# module.net
KiCad netlist of a schematic drawn in EAGLE
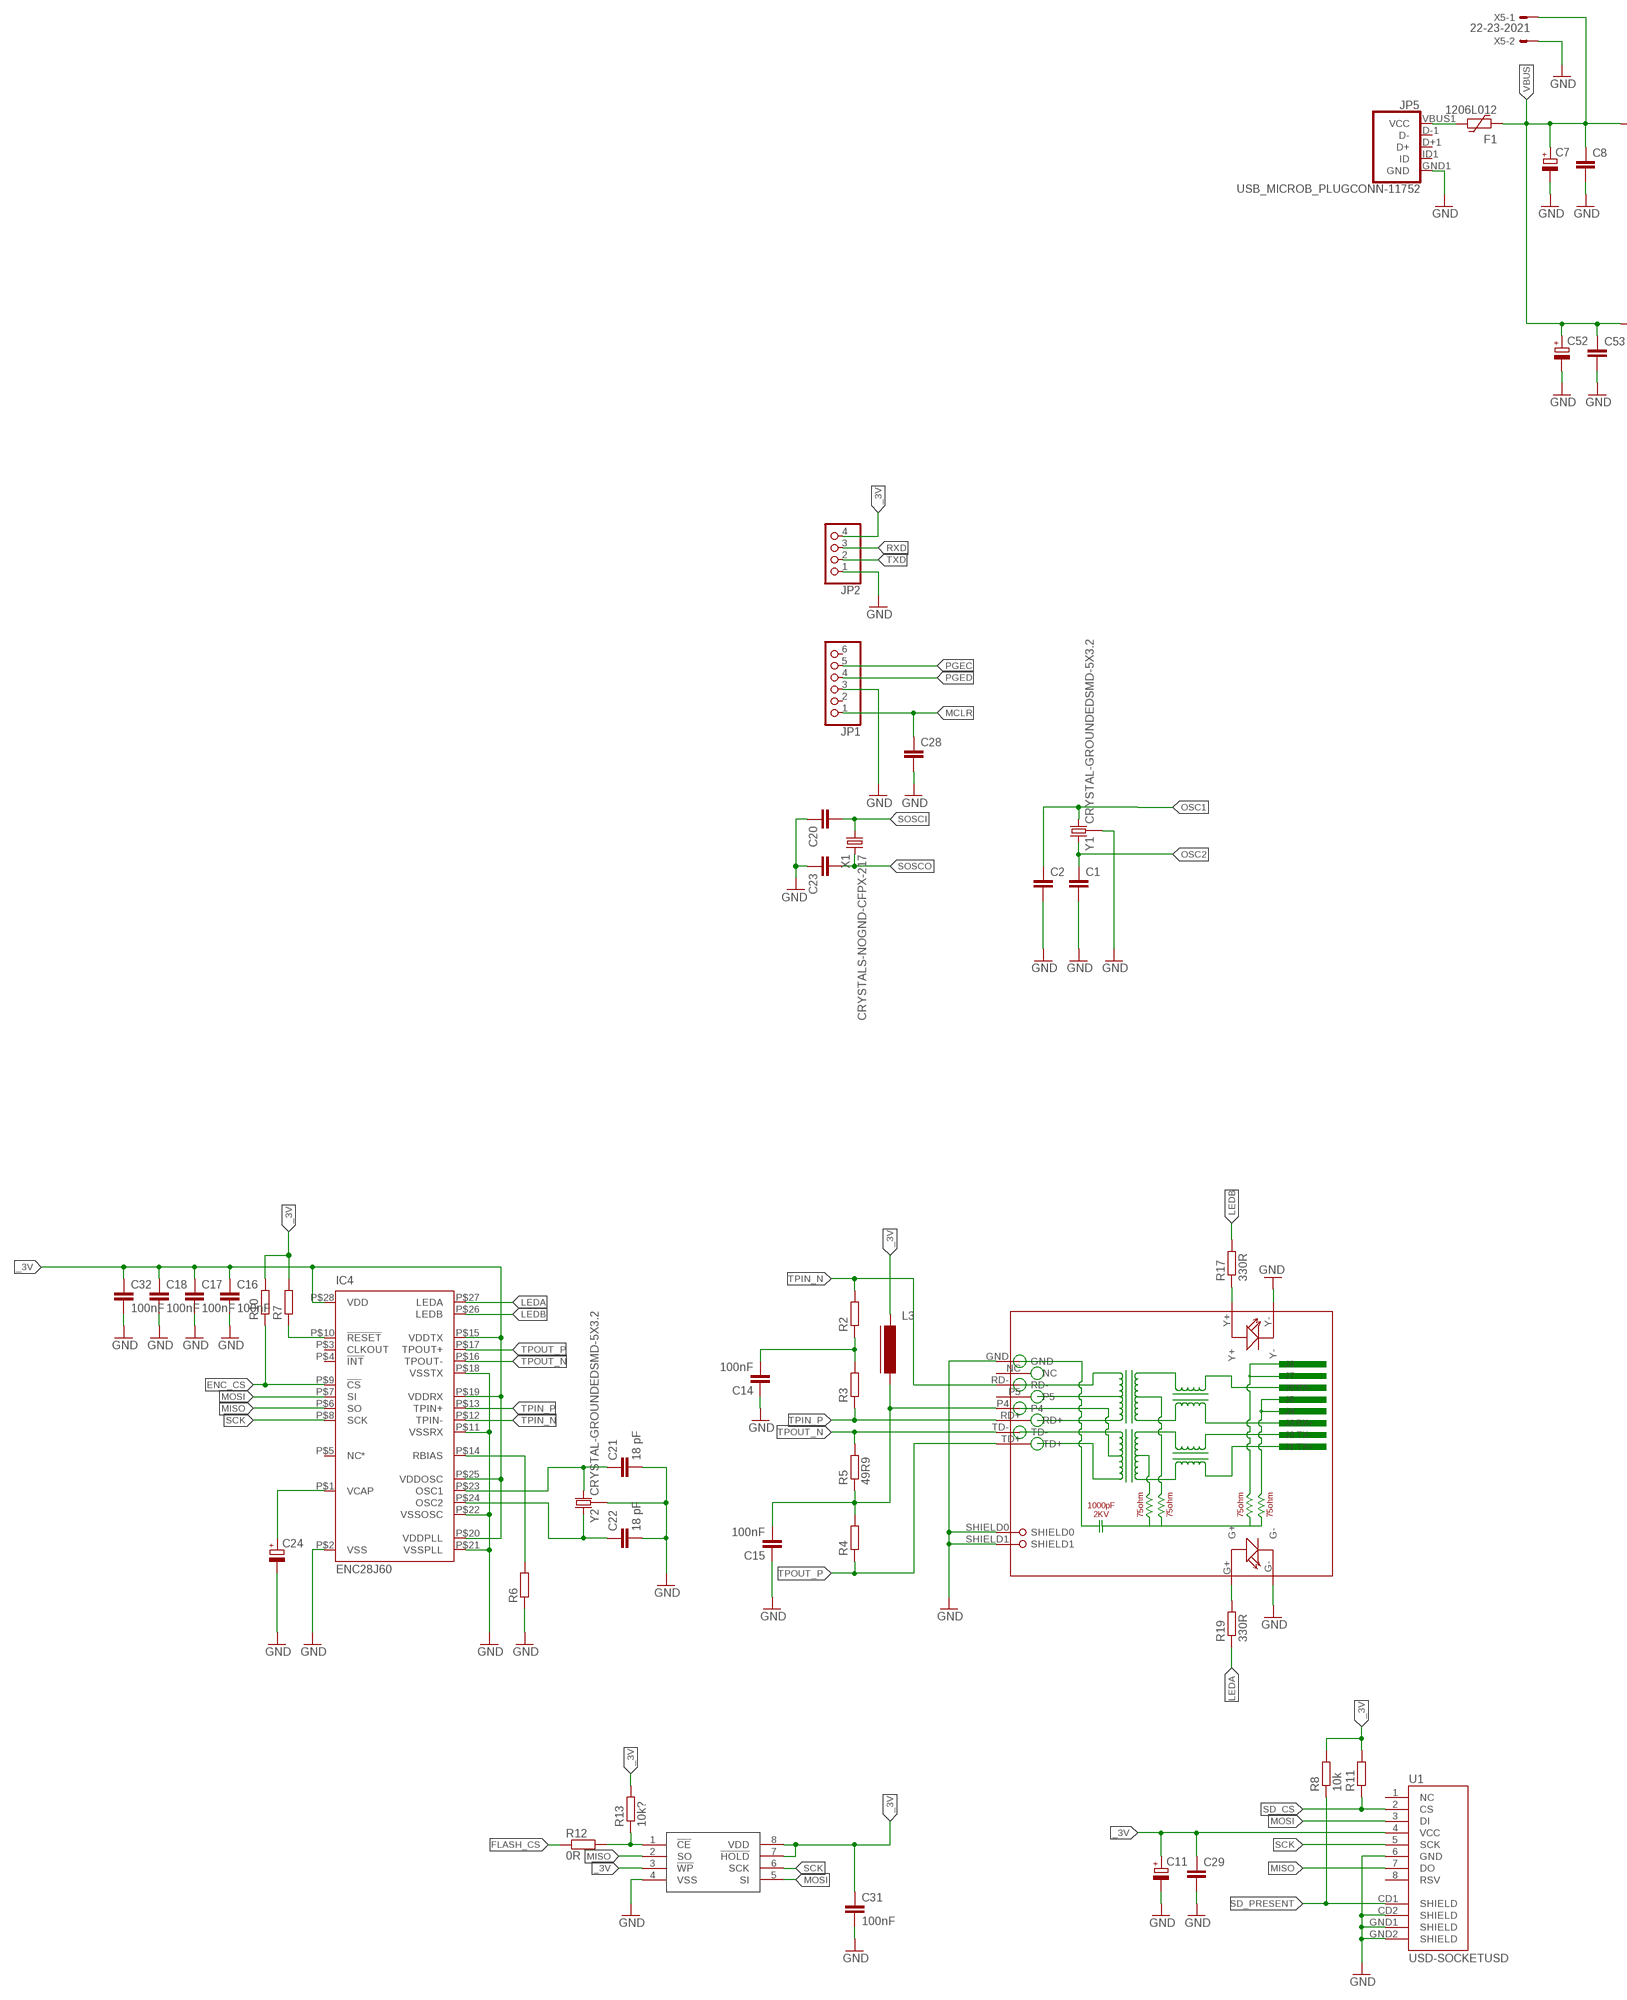
[diagram p0: schematic, sheet 1, part 1 of 3]
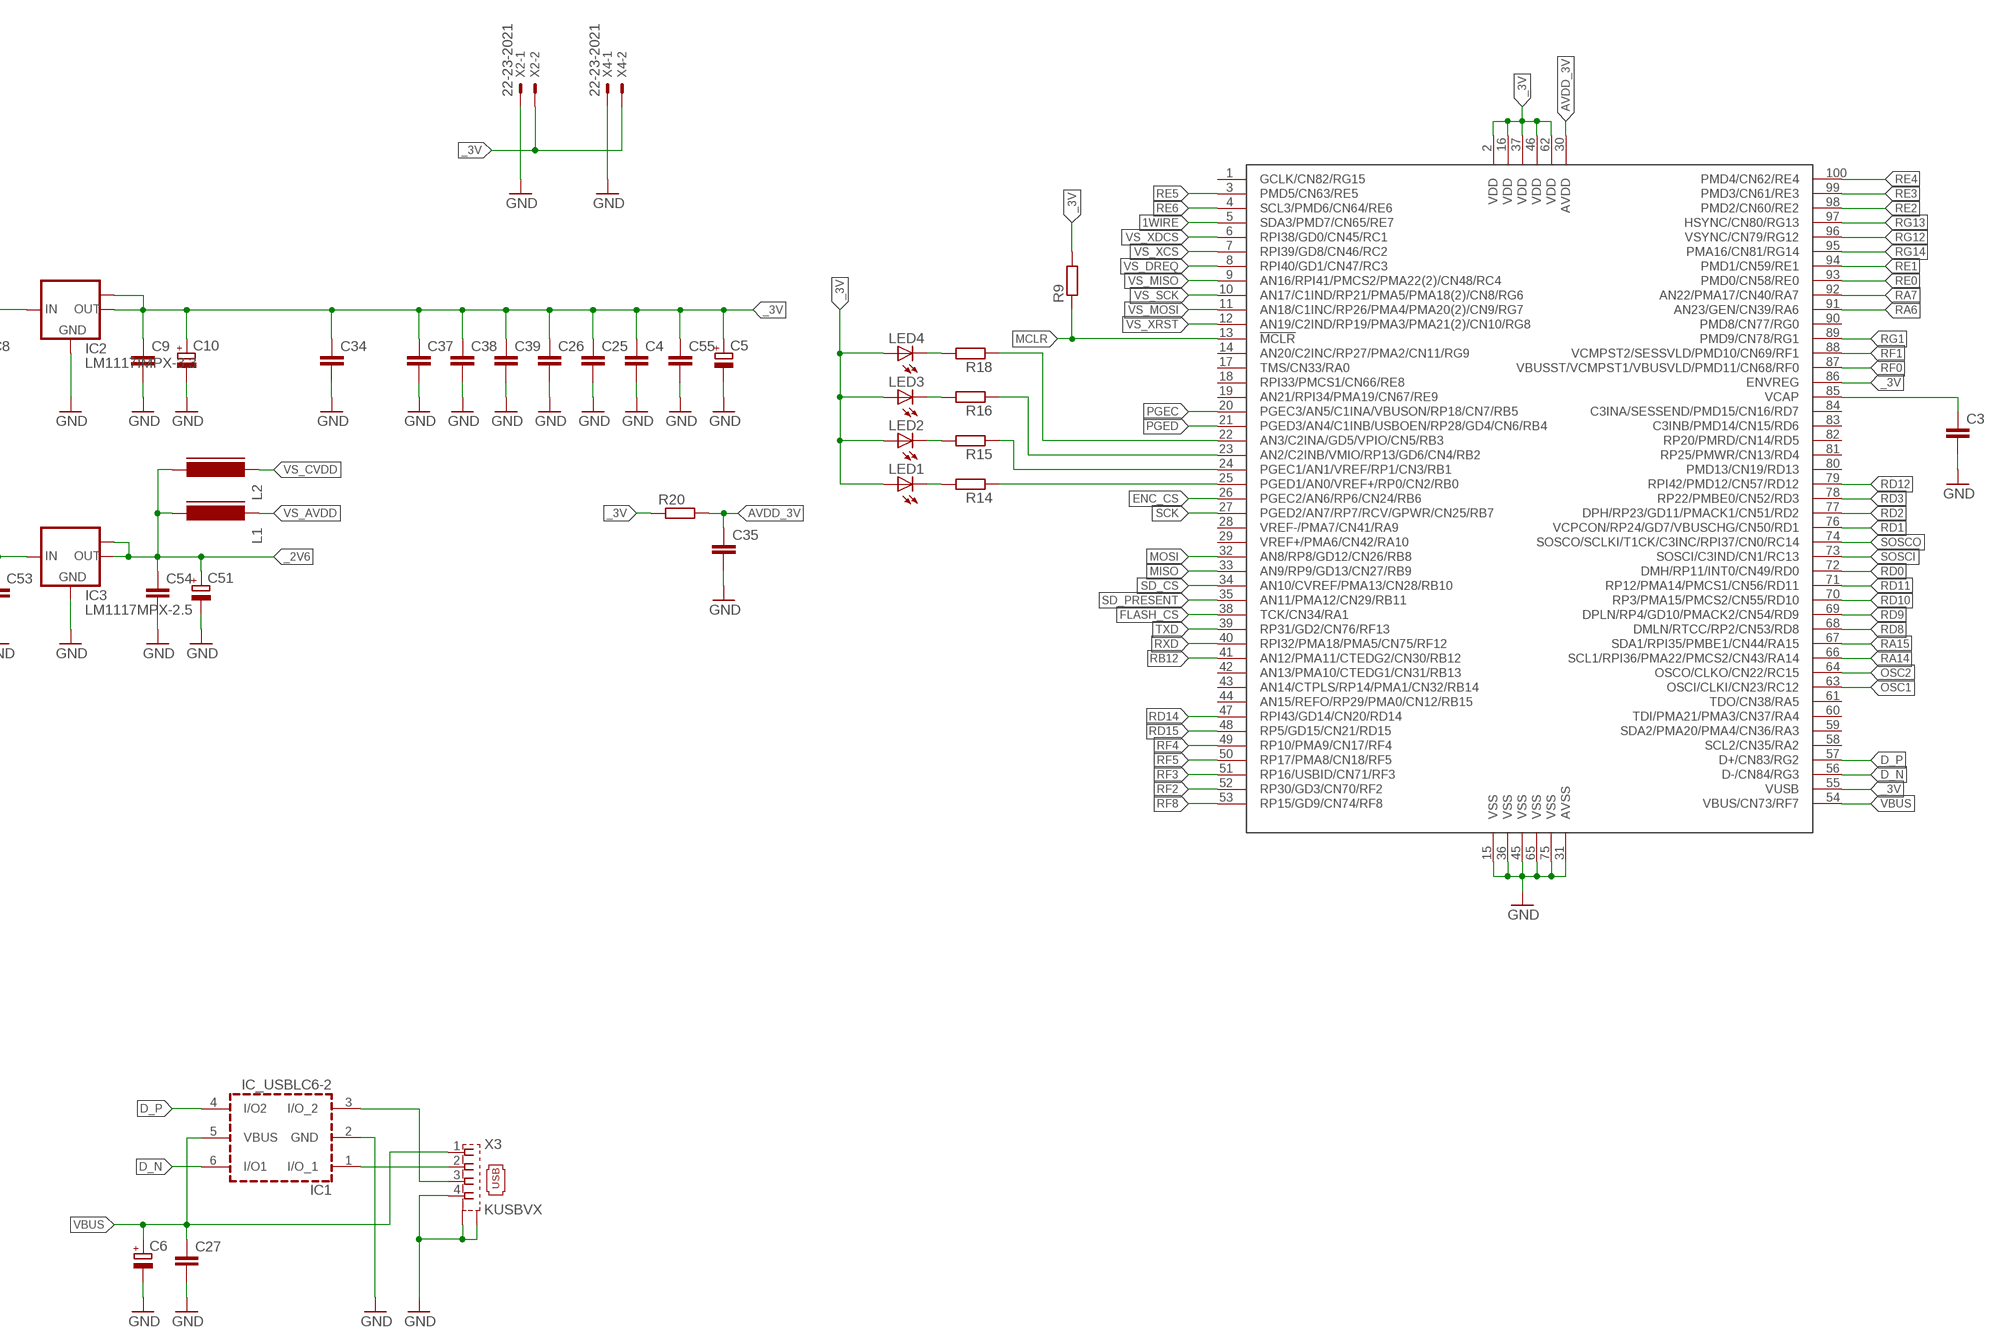
[diagram p1: schematic, sheet 1, part 2 of 3]
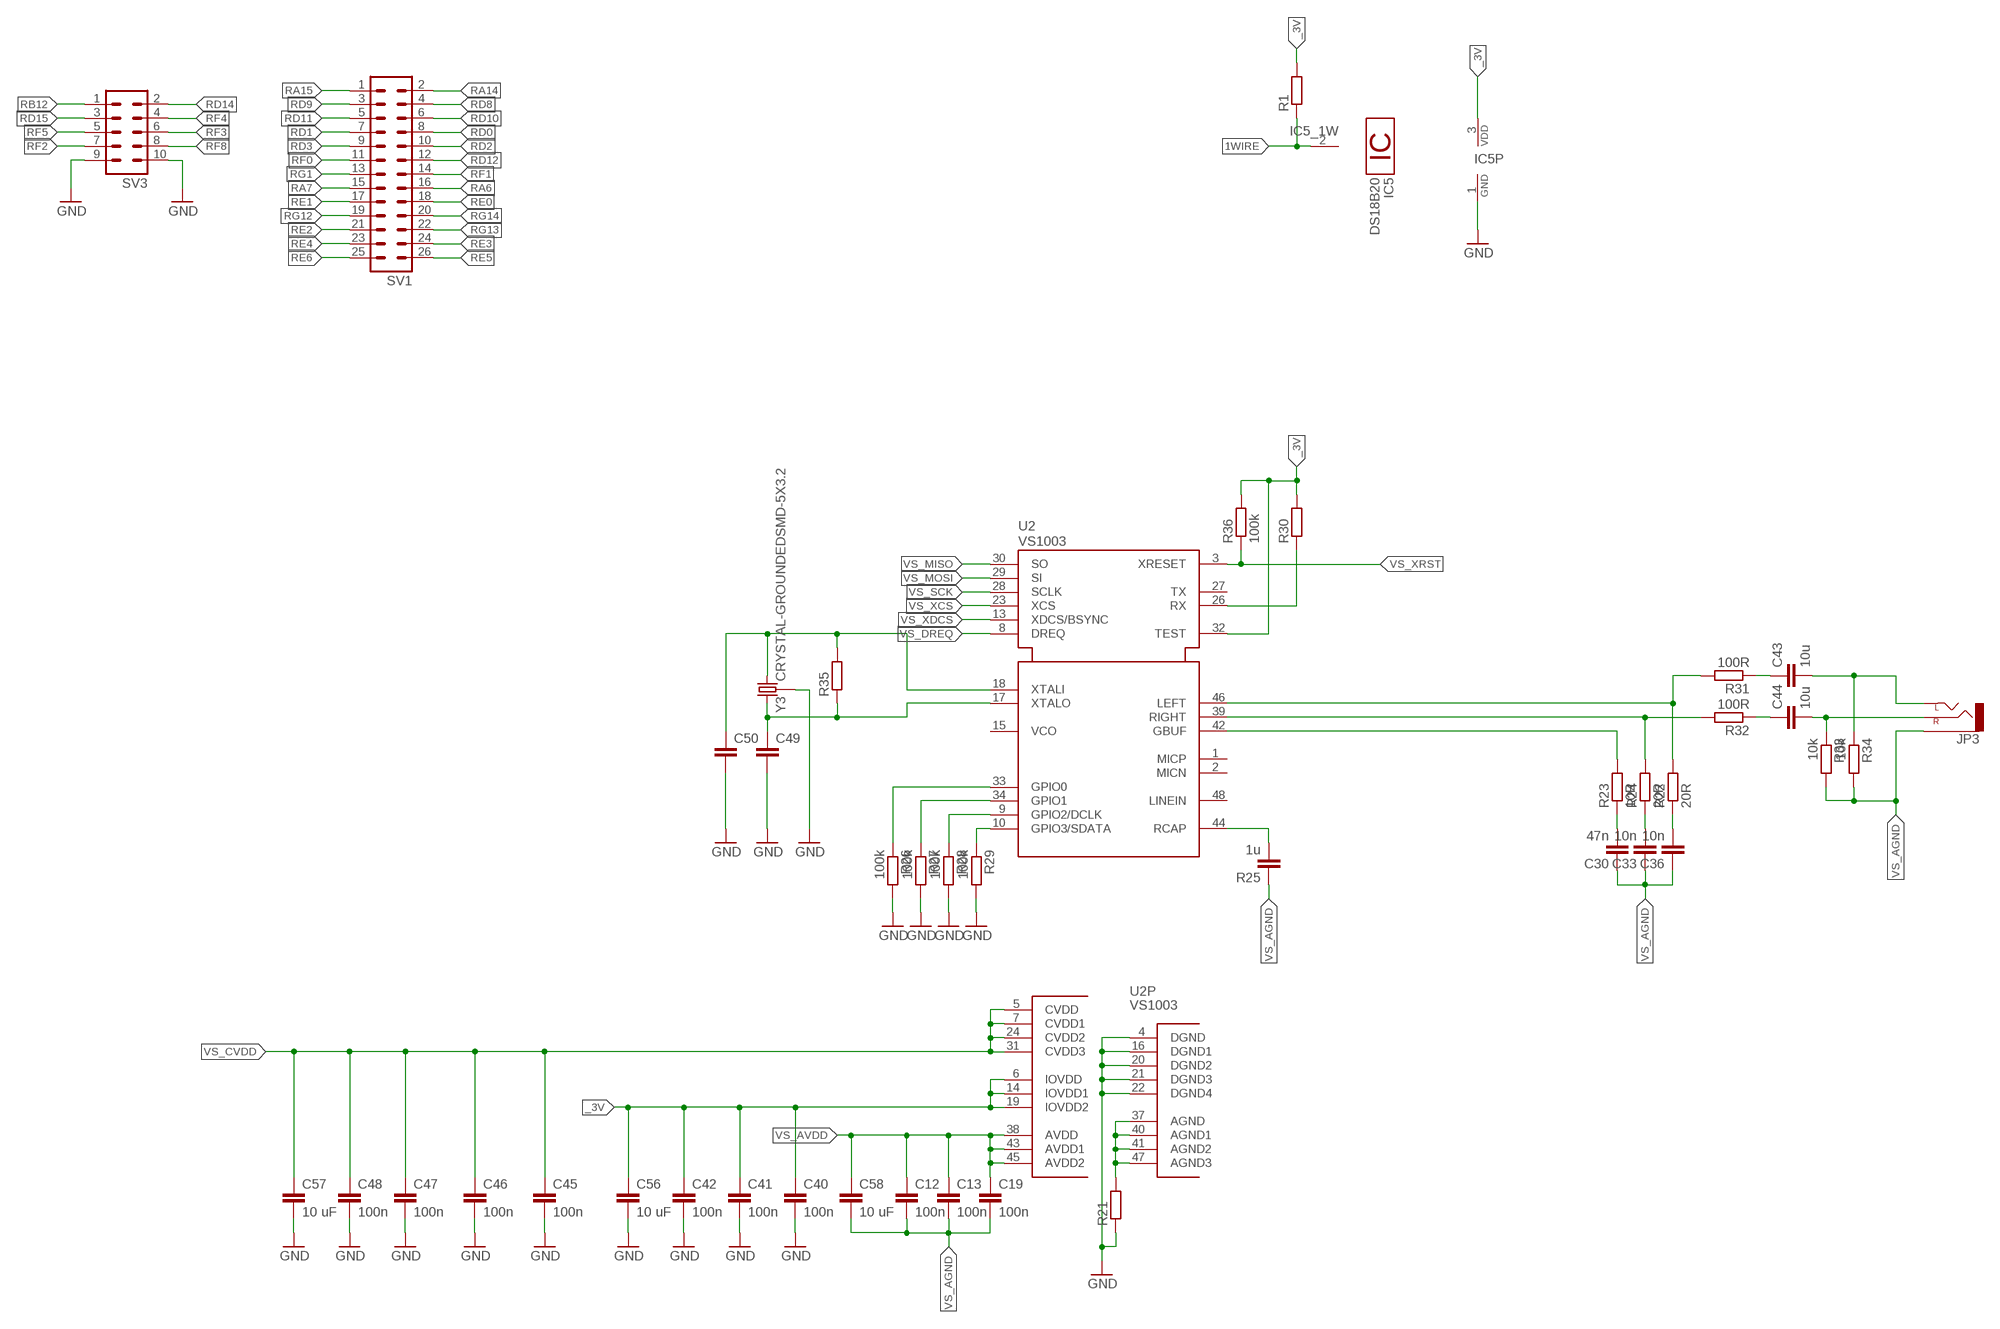
[diagram p2: schematic, sheet 1, part 3 of 3]

(export (version "E")
  (design (tool "Eeschema 10.0.6"))
  (components
    (comp (ref "C1")
      (value "C-EUC0603")
      (footprint "eagle-import:C0603")
      (libsource (lib "eagle-import") (part "C-EUC0603"))
    )
    (comp (ref "C2")
      (value "C-EUC0603")
      (footprint "eagle-import:C0603")
      (libsource (lib "eagle-import") (part "C-EUC0603"))
    )
    (comp (ref "C3")
      (value "C-EUC0603")
      (footprint "eagle-import:C0603")
      (libsource (lib "eagle-import") (part "C-EUC0603"))
    )
    (comp (ref "C4")
      (value "C-EUC0402")
      (footprint "eagle-import:C0402")
      (libsource (lib "eagle-import") (part "C-EUC0402"))
    )
    (comp (ref "C5")
      (value "CPOL-EUSMCA")
      (footprint "eagle-import:SMC_A")
      (libsource (lib "eagle-import") (part "CPOL-EUSMCA"))
    )
    (comp (ref "C6")
      (value "CPOL-EUSMCB")
      (footprint "eagle-import:SMC_B")
      (libsource (lib "eagle-import") (part "CPOL-EUSMCB"))
    )
    (comp (ref "C7")
      (value "CPOL-EUSMCB")
      (footprint "eagle-import:SMC_B")
      (libsource (lib "eagle-import") (part "CPOL-EUSMCB"))
    )
    (comp (ref "C8")
      (value "C-EUC0603")
      (footprint "eagle-import:C0603")
      (libsource (lib "eagle-import") (part "C-EUC0603"))
    )
    (comp (ref "C9")
      (value "C-EUC0603")
      (footprint "eagle-import:C0603")
      (libsource (lib "eagle-import") (part "C-EUC0603"))
    )
    (comp (ref "C10")
      (value "CPOL-EUSMCB")
      (footprint "eagle-import:SMC_B")
      (libsource (lib "eagle-import") (part "CPOL-EUSMCB"))
    )
    (comp (ref "C11")
      (value "CPOL-EUSMCA")
      (footprint "eagle-import:SMC_A")
      (libsource (lib "eagle-import") (part "CPOL-EUSMCA"))
    )
    (comp (ref "C12")
      (value "100n")
      (footprint "eagle-import:C0603")
      (libsource (lib "eagle-import") (part "C-EUC0603"))
    )
    (comp (ref "C13")
      (value "100n")
      (footprint "eagle-import:C0603")
      (libsource (lib "eagle-import") (part "C-EUC0603"))
    )
    (comp (ref "C14")
      (value "100nF")
      (footprint "eagle-import:C0603")
      (libsource (lib "eagle-import") (part "C-EUC0603"))
    )
    (comp (ref "C15")
      (value "100nF")
      (footprint "eagle-import:C0603")
      (libsource (lib "eagle-import") (part "C-EUC0603"))
    )
    (comp (ref "C16")
      (value "100nF")
      (footprint "eagle-import:C0402")
      (libsource (lib "eagle-import") (part "C-EUC0402"))
    )
    (comp (ref "C17")
      (value "100nF")
      (footprint "eagle-import:C0603")
      (libsource (lib "eagle-import") (part "C-EUC0603"))
    )
    (comp (ref "C18")
      (value "100nF")
      (footprint "eagle-import:C0603")
      (libsource (lib "eagle-import") (part "C-EUC0603"))
    )
    (comp (ref "C19")
      (value "100n")
      (footprint "eagle-import:C0603")
      (libsource (lib "eagle-import") (part "C-EUC0603"))
    )
    (comp (ref "C20")
      (value "C-EUC0603")
      (footprint "eagle-import:C0603")
      (libsource (lib "eagle-import") (part "C-EUC0603"))
    )
    (comp (ref "C21")
      (value "18 pF")
      (footprint "eagle-import:C0603")
      (libsource (lib "eagle-import") (part "C-EUC0603"))
    )
    (comp (ref "C22")
      (value "18 pF")
      (footprint "eagle-import:C0603")
      (libsource (lib "eagle-import") (part "C-EUC0603"))
    )
    (comp (ref "C23")
      (value "C-EUC0603")
      (footprint "eagle-import:C0603")
      (libsource (lib "eagle-import") (part "C-EUC0603"))
    )
    (comp (ref "C24")
      (value "CPOL-EUSMCA")
      (footprint "eagle-import:SMC_A")
      (libsource (lib "eagle-import") (part "CPOL-EUSMCA"))
    )
    (comp (ref "C25")
      (value "C-EUC0402")
      (footprint "eagle-import:C0402")
      (libsource (lib "eagle-import") (part "C-EUC0402"))
    )
    (comp (ref "C26")
      (value "C-EUC0402")
      (footprint "eagle-import:C0402")
      (libsource (lib "eagle-import") (part "C-EUC0402"))
    )
    (comp (ref "C27")
      (value "C-EUC0805")
      (footprint "eagle-import:C0805")
      (libsource (lib "eagle-import") (part "C-EUC0805"))
    )
    (comp (ref "C28")
      (value "C-EUC0603")
      (footprint "eagle-import:C0603")
      (libsource (lib "eagle-import") (part "C-EUC0603"))
    )
    (comp (ref "C29")
      (value "C-EUC0603")
      (footprint "eagle-import:C0603")
      (libsource (lib "eagle-import") (part "C-EUC0603"))
    )
    (comp (ref "C30")
      (value "47n")
      (footprint "eagle-import:C0603")
      (libsource (lib "eagle-import") (part "C-EUC0603"))
    )
    (comp (ref "C31")
      (value "100nF")
      (footprint "eagle-import:C0603")
      (libsource (lib "eagle-import") (part "C-EUC0603"))
    )
    (comp (ref "C32")
      (value "100nF")
      (footprint "eagle-import:C0402")
      (libsource (lib "eagle-import") (part "C-EUC0402"))
    )
    (comp (ref "C33")
      (value "10n")
      (footprint "eagle-import:C0603")
      (libsource (lib "eagle-import") (part "C-EUC0603"))
    )
    (comp (ref "C34")
      (value "C-EUC0402")
      (footprint "eagle-import:C0402")
      (libsource (lib "eagle-import") (part "C-EUC0402"))
    )
    (comp (ref "C35")
      (value "C-EUC0402")
      (footprint "eagle-import:C0402")
      (libsource (lib "eagle-import") (part "C-EUC0402"))
    )
    (comp (ref "C36")
      (value "10n")
      (footprint "eagle-import:C0603")
      (libsource (lib "eagle-import") (part "C-EUC0603"))
    )
    (comp (ref "C37")
      (value "C-EUC0402")
      (footprint "eagle-import:C0402")
      (libsource (lib "eagle-import") (part "C-EUC0402"))
    )
    (comp (ref "C38")
      (value "C-EUC0603")
      (footprint "eagle-import:C0603")
      (libsource (lib "eagle-import") (part "C-EUC0603"))
    )
    (comp (ref "C39")
      (value "C-EUC0402")
      (footprint "eagle-import:C0402")
      (libsource (lib "eagle-import") (part "C-EUC0402"))
    )
    (comp (ref "C40")
      (value "100n")
      (footprint "eagle-import:C0402")
      (libsource (lib "eagle-import") (part "C-EUC0402"))
    )
    (comp (ref "C41")
      (value "100n")
      (footprint "eagle-import:C0402")
      (libsource (lib "eagle-import") (part "C-EUC0402"))
    )
    (comp (ref "C42")
      (value "100n")
      (footprint "eagle-import:C0402")
      (libsource (lib "eagle-import") (part "C-EUC0402"))
    )
    (comp (ref "C43")
      (value "10u")
      (footprint "eagle-import:C0603")
      (libsource (lib "eagle-import") (part "C-EUC0603"))
    )
    (comp (ref "C44")
      (value "10u")
      (footprint "eagle-import:C0603")
      (libsource (lib "eagle-import") (part "C-EUC0603"))
    )
    (comp (ref "C45")
      (value "100n")
      (footprint "eagle-import:C0402")
      (libsource (lib "eagle-import") (part "C-EUC0402"))
    )
    (comp (ref "C46")
      (value "100n")
      (footprint "eagle-import:C0603")
      (libsource (lib "eagle-import") (part "C-EUC0603"))
    )
    (comp (ref "C47")
      (value "100n")
      (footprint "eagle-import:C0603")
      (libsource (lib "eagle-import") (part "C-EUC0603"))
    )
    (comp (ref "C48")
      (value "100n")
      (footprint "eagle-import:C0603")
      (libsource (lib "eagle-import") (part "C-EUC0603"))
    )
    (comp (ref "C49")
      (value "C-EUC0603")
      (footprint "eagle-import:C0603")
      (libsource (lib "eagle-import") (part "C-EUC0603"))
    )
    (comp (ref "C50")
      (value "C-EUC0603")
      (footprint "eagle-import:C0603")
      (libsource (lib "eagle-import") (part "C-EUC0603"))
    )
    (comp (ref "C51")
      (value "CPOL-EUSMCC")
      (footprint "eagle-import:SMC_C")
      (libsource (lib "eagle-import") (part "CPOL-EUSMCC"))
    )
    (comp (ref "C52")
      (value "CPOL-EUSMCC")
      (footprint "eagle-import:SMC_C")
      (libsource (lib "eagle-import") (part "CPOL-EUSMCC"))
    )
    (comp (ref "C53")
      (value "C-EUC1206")
      (footprint "eagle-import:C1206")
      (libsource (lib "eagle-import") (part "C-EUC1206"))
    )
    (comp (ref "C54")
      (value "C-EUC1206")
      (footprint "eagle-import:C1206")
      (libsource (lib "eagle-import") (part "C-EUC1206"))
    )
    (comp (ref "C55")
      (value "C-EUC0603")
      (footprint "eagle-import:C0603")
      (libsource (lib "eagle-import") (part "C-EUC0603"))
    )
    (comp (ref "C56")
      (value "10 uF")
      (footprint "eagle-import:C0603")
      (libsource (lib "eagle-import") (part "C-EUC0603"))
    )
    (comp (ref "C57")
      (value "10 uF")
      (footprint "eagle-import:C0603")
      (libsource (lib "eagle-import") (part "C-EUC0603"))
    )
    (comp (ref "C58")
      (value "10 uF")
      (footprint "eagle-import:C0603")
      (libsource (lib "eagle-import") (part "C-EUC0603"))
    )
    (comp (ref "F1")
      (value "1206L012")
      (footprint "eagle-import:1206L")
      (fields (field (name "MF") "Littelfuse"))
      (libsource (lib "eagle-import") (part "?1206L012"))
    )
    (comp (ref "IC1")
      (value "IC_USBLC6-2")
      (footprint "eagle-import:SOT-23-6L")
      (libsource (lib "eagle-import") (part "IC_USBLC6-2"))
    )
    (comp (ref "IC2")
      (value "LM1117IMPX-3.3")
      (footprint "eagle-import:SOT223")
      (libsource (lib "eagle-import") (part "LM1117IMPX-3.3"))
    )
    (comp (ref "IC3")
      (value "LM1117MPX-2.5")
      (footprint "eagle-import:SOT223")
      (libsource (lib "eagle-import") (part "LM1117MPX-2.5"))
    )
    (comp (ref "IC4")
      (value "ENC28J60")
      (footprint "eagle-import:TSSOP28W")
      (libsource (lib "eagle-import") (part "ENC28J60"))
    )
    (comp (ref "IC5")
      (value "DS18B20")
      (footprint "eagle-import:TO92-")
      (libsource (lib "eagle-import") (part "DS18B20"))
    )
    (comp (ref "JP1")
      (value "PINHD-1X6")
      (footprint "eagle-import:1X06")
      (libsource (lib "eagle-import") (part "PINHD-1X6"))
    )
    (comp (ref "JP2")
      (value "PINHD-1X4")
      (footprint "eagle-import:1X04")
      (libsource (lib "eagle-import") (part "PINHD-1X4"))
    )
    (comp (ref "JP3")
      (value "AUDIO-JACKAUDIO_JACK2")
      (footprint "eagle-import:AUDIO-JACK2")
      (libsource (lib "eagle-import") (part "AUDIO-JACKAUDIO_JACK2"))
    )
    (comp (ref "JP5")
      (value "USB_MICROB_PLUGCONN-11752")
      (footprint "eagle-import:USB-B-MICRO-SMD_V03")
      (libsource (lib "eagle-import") (part "USB_MICROB_PLUGCONN-11752"))
    )
    (comp (ref "L1")
      (value "FERRITE-0805")
      (footprint "eagle-import:FB805")
      (libsource (lib "eagle-import") (part "FERRITE-0805"))
    )
    (comp (ref "L2")
      (value "FERRITE-0805")
      (footprint "eagle-import:FB805")
      (libsource (lib "eagle-import") (part "FERRITE-0805"))
    )
    (comp (ref "L3")
      (value "FERRITE-0805")
      (footprint "eagle-import:FB805")
      (libsource (lib "eagle-import") (part "FERRITE-0805"))
    )
    (comp (ref "LED1")
      (value "LEDCHIP-LED0603")
      (footprint "eagle-import:CHIP-LED0603")
      (libsource (lib "eagle-import") (part "LEDCHIP-LED0603"))
    )
    (comp (ref "LED2")
      (value "LEDCHIP-LED0603")
      (footprint "eagle-import:CHIP-LED0603")
      (libsource (lib "eagle-import") (part "LEDCHIP-LED0603"))
    )
    (comp (ref "LED3")
      (value "LEDCHIP-LED0603")
      (footprint "eagle-import:CHIP-LED0603")
      (libsource (lib "eagle-import") (part "LEDCHIP-LED0603"))
    )
    (comp (ref "LED4")
      (value "LEDCHIP-LED0603")
      (footprint "eagle-import:CHIP-LED0603")
      (libsource (lib "eagle-import") (part "LEDCHIP-LED0603"))
    )
    (comp (ref "R1")
      (value "R-EU_R0603")
      (footprint "eagle-import:R0603")
      (libsource (lib "eagle-import") (part "R-EU_R0603"))
    )
    (comp (ref "R2")
      (value "R-EU_R0603")
      (footprint "eagle-import:R0603")
      (libsource (lib "eagle-import") (part "R-EU_R0603"))
    )
    (comp (ref "R3")
      (value "R-EU_R0603")
      (footprint "eagle-import:R0603")
      (libsource (lib "eagle-import") (part "R-EU_R0603"))
    )
    (comp (ref "R4")
      (value "R-EU_R0603")
      (footprint "eagle-import:R0603")
      (libsource (lib "eagle-import") (part "R-EU_R0603"))
    )
    (comp (ref "R5")
      (value "49R9")
      (footprint "eagle-import:R0603")
      (libsource (lib "eagle-import") (part "R-EU_R0603"))
    )
    (comp (ref "R6")
      (value "R-EU_R0805")
      (footprint "eagle-import:R0805")
      (libsource (lib "eagle-import") (part "R-EU_R0805"))
    )
    (comp (ref "R7")
      (value "R-EU_R0603")
      (footprint "eagle-import:R0603")
      (libsource (lib "eagle-import") (part "R-EU_R0603"))
    )
    (comp (ref "R8")
      (value "10k")
      (footprint "eagle-import:R0603")
      (libsource (lib "eagle-import") (part "R-EU_R0603"))
    )
    (comp (ref "R9")
      (value "R-EU_R0603")
      (footprint "eagle-import:R0603")
      (libsource (lib "eagle-import") (part "R-EU_R0603"))
    )
    (comp (ref "R10")
      (value "R-EU_R0603")
      (footprint "eagle-import:R0603")
      (libsource (lib "eagle-import") (part "R-EU_R0603"))
    )
    (comp (ref "R11")
      (value "R-EU_R0603")
      (footprint "eagle-import:R0603")
      (libsource (lib "eagle-import") (part "R-EU_R0603"))
    )
    (comp (ref "R12")
      (value "0R")
      (footprint "eagle-import:R0603")
      (libsource (lib "eagle-import") (part "R-EU_R0603"))
    )
    (comp (ref "R13")
      (value "10k?")
      (footprint "eagle-import:R0603")
      (libsource (lib "eagle-import") (part "R-EU_R0603"))
    )
    (comp (ref "R14")
      (value "R-EU_R0603")
      (footprint "eagle-import:R0603")
      (libsource (lib "eagle-import") (part "R-EU_R0603"))
    )
    (comp (ref "R15")
      (value "R-EU_R0603")
      (footprint "eagle-import:R0603")
      (libsource (lib "eagle-import") (part "R-EU_R0603"))
    )
    (comp (ref "R16")
      (value "R-EU_R0603")
      (footprint "eagle-import:R0603")
      (libsource (lib "eagle-import") (part "R-EU_R0603"))
    )
    (comp (ref "R17")
      (value "330R")
      (footprint "eagle-import:R1206")
      (libsource (lib "eagle-import") (part "R-EU_R1206"))
    )
    (comp (ref "R18")
      (value "R-EU_R0603")
      (footprint "eagle-import:R0603")
      (libsource (lib "eagle-import") (part "R-EU_R0603"))
    )
    (comp (ref "R19")
      (value "330R")
      (footprint "eagle-import:R1206")
      (libsource (lib "eagle-import") (part "R-EU_R1206"))
    )
    (comp (ref "R20")
      (value "R-EU_R0805")
      (footprint "eagle-import:R0805")
      (libsource (lib "eagle-import") (part "R-EU_R0805"))
    )
    (comp (ref "R21")
      (value "R-EU_R0603")
      (footprint "eagle-import:R0603")
      (libsource (lib "eagle-import") (part "R-EU_R0603"))
    )
    (comp (ref "R22")
      (value "20R")
      (footprint "eagle-import:R0603")
      (libsource (lib "eagle-import") (part "R-EU_R0603"))
    )
    (comp (ref "R23")
      (value "10R")
      (footprint "eagle-import:R0603")
      (libsource (lib "eagle-import") (part "R-EU_R0603"))
    )
    (comp (ref "R24")
      (value "20R")
      (footprint "eagle-import:R0603")
      (libsource (lib "eagle-import") (part "R-EU_R0603"))
    )
    (comp (ref "R25")
      (value "1u")
      (footprint "eagle-import:C0603")
      (libsource (lib "eagle-import") (part "C-EUC0603"))
    )
    (comp (ref "R26")
      (value "100k")
      (footprint "eagle-import:R0402")
      (libsource (lib "eagle-import") (part "R-EU_R0402"))
    )
    (comp (ref "R27")
      (value "100k")
      (footprint "eagle-import:R0402")
      (libsource (lib "eagle-import") (part "R-EU_R0402"))
    )
    (comp (ref "R28")
      (value "100k")
      (footprint "eagle-import:R0402")
      (libsource (lib "eagle-import") (part "R-EU_R0402"))
    )
    (comp (ref "R29")
      (value "100k")
      (footprint "eagle-import:R0402")
      (libsource (lib "eagle-import") (part "R-EU_R0402"))
    )
    (comp (ref "R30")
      (value "R-EU_0204/7")
      (footprint "eagle-import:0204_7")
      (libsource (lib "eagle-import") (part "R-EU_0204/7"))
    )
    (comp (ref "R31")
      (value "100R")
      (footprint "eagle-import:R0603")
      (libsource (lib "eagle-import") (part "R-EU_R0603"))
    )
    (comp (ref "R32")
      (value "100R")
      (footprint "eagle-import:R0603")
      (libsource (lib "eagle-import") (part "R-EU_R0603"))
    )
    (comp (ref "R33")
      (value "10k")
      (footprint "eagle-import:R0603")
      (libsource (lib "eagle-import") (part "R-EU_R0603"))
    )
    (comp (ref "R34")
      (value "10k")
      (footprint "eagle-import:R0603")
      (libsource (lib "eagle-import") (part "R-EU_R0603"))
    )
    (comp (ref "R35")
      (value "R-EU_R0603")
      (footprint "eagle-import:R0603")
      (libsource (lib "eagle-import") (part "R-EU_R0603"))
    )
    (comp (ref "R36")
      (value "100k")
      (footprint "eagle-import:R0603")
      (libsource (lib "eagle-import") (part "R-EU_R0603"))
    )
    (comp (ref "RJ1")
      (value "HR911105A")
      (footprint "eagle-import:HR911105A")
      (libsource (lib "eagle-import") (part "HR911105A"))
    )
    (comp (ref "SV1")
      (value "ML26L")
      (footprint "eagle-import:ML26L")
      (libsource (lib "eagle-import") (part "ML26L"))
    )
    (comp (ref "SV3")
      (value "ML10L")
      (footprint "eagle-import:ML10L")
      (libsource (lib "eagle-import") (part "ML10L"))
    )
    (comp (ref "U$1")
      (value "PIC24FJ256DA210SMALL")
      (footprint "eagle-import:TQFP100-12X12")
      (libsource (lib "eagle-import") (part "PIC24FJ256DA210SMALL"))
    )
    (comp (ref "U$2")
      (value "SST25VF016BSO8M")
      (footprint "eagle-import:SO-08M")
      (libsource (lib "eagle-import") (part "SST25VF016BSO8M"))
    )
    (comp (ref "U1")
      (value "USD-SOCKETUSD")
      (footprint "eagle-import:USD-SOCKET-PP")
      (libsource (lib "eagle-import") (part "USD-SOCKETUSD"))
    )
    (comp (ref "U2")
      (value "VS1003")
      (footprint "eagle-import:LQFP48")
      (libsource (lib "eagle-import") (part "VS1003"))
    )
    (comp (ref "X1")
      (value "CRYSTALS-NOGND-CFPX-217")
      (footprint "eagle-import:3.2X1.5-2-PAD")
      (libsource (lib "eagle-import") (part "CRYSTALS-NOGND-CFPX-217"))
    )
    (comp (ref "X2")
      (value "22-23-2021")
      (footprint "eagle-import:22-23-2021")
      (fields (field (name "MF") "MOLEX"))
      (libsource (lib "eagle-import") (part "22-23-2021"))
    )
    (comp (ref "X3")
      (value "KUSBVX")
      (footprint "eagle-import:KUSBVX")
      (libsource (lib "eagle-import") (part "KUSBVX"))
    )
    (comp (ref "X4")
      (value "22-23-2021")
      (footprint "eagle-import:22-23-2021")
      (fields (field (name "MF") "MOLEX"))
      (libsource (lib "eagle-import") (part "22-23-2021"))
    )
    (comp (ref "X5")
      (value "22-23-2021")
      (footprint "eagle-import:22-23-2021")
      (fields (field (name "MF") "MOLEX"))
      (libsource (lib "eagle-import") (part "22-23-2021"))
    )
    (comp (ref "Y1")
      (value "CRYSTAL-GROUNDEDSMD-5X3.2")
      (footprint "eagle-import:CRYSTAL-SMD-5X3.2-4PAD")
      (libsource (lib "eagle-import") (part "CRYSTAL-GROUNDEDSMD-5X3.2"))
    )
    (comp (ref "Y2")
      (value "CRYSTAL-GROUNDEDSMD-5X3.2")
      (footprint "eagle-import:CRYSTAL-SMD-5X3.2-4PAD")
      (libsource (lib "eagle-import") (part "CRYSTAL-GROUNDEDSMD-5X3.2"))
    )
    (comp (ref "Y3")
      (value "CRYSTAL-GROUNDEDSMD-5X3.2")
      (footprint "eagle-import:CRYSTAL-SMD-5X3.2-4PAD")
      (libsource (lib "eagle-import") (part "CRYSTAL-GROUNDEDSMD-5X3.2"))
    )
  )
  (nets
    (net (code "1") (name "1WIRE") (class "Default")
      (node (ref "IC5") (pin "2") (pinfunction "1W_2") (pintype "power_in"))
      (node (ref "R1") (pin "1") (pinfunction "1_1") (pintype "passive"))
      (node (ref "U$1") (pin "5") (pinfunction "SDA3/PMD7/CN65/RE7_5") (pintype "bidirectional"))
    )
    (net (code "2") (name "AVDD_3V") (class "Default")
      (node (ref "C35") (pin "1") (pinfunction "1_1") (pintype "passive"))
      (node (ref "R20") (pin "2") (pinfunction "2_2") (pintype "passive"))
      (node (ref "U$1") (pin "30") (pinfunction "AVDD_30") (pintype "bidirectional"))
    )
    (net (code "3") (name "D_N") (class "Default")
      (node (ref "IC1") (pin "6") (pinfunction "I/O1_6") (pintype "bidirectional"))
      (node (ref "U$1") (pin "56") (pinfunction "D-/CN84/RG3_56") (pintype "bidirectional"))
    )
    (net (code "4") (name "D_P") (class "Default")
      (node (ref "IC1") (pin "4") (pinfunction "I/O2_4") (pintype "bidirectional"))
      (node (ref "U$1") (pin "57") (pinfunction "D+/CN83/RG2_57") (pintype "bidirectional"))
    )
    (net (code "5") (name "ENC_CS") (class "Default")
      (node (ref "IC4") (pin "P$9") (pinfunction "~{CS}_P$9") (pintype "input"))
      (node (ref "R10") (pin "1") (pinfunction "1_1") (pintype "passive"))
      (node (ref "U$1") (pin "26") (pinfunction "PGEC2/AN6/RP6/CN24/RB6_26") (pintype "bidirectional"))
    )
    (net (code "6") (name "FLASH_CS") (class "Default")
      (node (ref "R12") (pin "1") (pinfunction "1_1") (pintype "passive"))
      (node (ref "U$1") (pin "38") (pinfunction "TCK/CN34/RA1_38") (pintype "bidirectional"))
    )
    (net (code "7") (name "GND") (class "Default")
      (node (ref "C1") (pin "2") (pinfunction "2_2") (pintype "passive"))
      (node (ref "C10") (pin "-") (pinfunction "-_-") (pintype "passive"))
      (node (ref "C11") (pin "-") (pinfunction "-_-") (pintype "passive"))
      (node (ref "C14") (pin "1") (pinfunction "1_1") (pintype "passive"))
      (node (ref "C15") (pin "1") (pinfunction "1_1") (pintype "passive"))
      (node (ref "C16") (pin "2") (pinfunction "2_2") (pintype "passive"))
      (node (ref "C17") (pin "2") (pinfunction "2_2") (pintype "passive"))
      (node (ref "C18") (pin "2") (pinfunction "2_2") (pintype "passive"))
      (node (ref "C2") (pin "2") (pinfunction "2_2") (pintype "passive"))
      (node (ref "C20") (pin "1") (pinfunction "1_1") (pintype "passive"))
      (node (ref "C21") (pin "2") (pinfunction "2_2") (pintype "passive"))
      (node (ref "C22") (pin "2") (pinfunction "2_2") (pintype "passive"))
      (node (ref "C23") (pin "1") (pinfunction "1_1") (pintype "passive"))
      (node (ref "C24") (pin "-") (pinfunction "-_-") (pintype "passive"))
      (node (ref "C25") (pin "2") (pinfunction "2_2") (pintype "passive"))
      (node (ref "C26") (pin "2") (pinfunction "2_2") (pintype "passive"))
      (node (ref "C27") (pin "2") (pinfunction "2_2") (pintype "passive"))
      (node (ref "C28") (pin "2") (pinfunction "2_2") (pintype "passive"))
      (node (ref "C29") (pin "2") (pinfunction "2_2") (pintype "passive"))
      (node (ref "C3") (pin "2") (pinfunction "2_2") (pintype "passive"))
      (node (ref "C31") (pin "2") (pinfunction "2_2") (pintype "passive"))
      (node (ref "C32") (pin "2") (pinfunction "2_2") (pintype "passive"))
      (node (ref "C34") (pin "2") (pinfunction "2_2") (pintype "passive"))
      (node (ref "C35") (pin "2") (pinfunction "2_2") (pintype "passive"))
      (node (ref "C37") (pin "2") (pinfunction "2_2") (pintype "passive"))
      (node (ref "C38") (pin "2") (pinfunction "2_2") (pintype "passive"))
      (node (ref "C39") (pin "2") (pinfunction "2_2") (pintype "passive"))
      (node (ref "C4") (pin "2") (pinfunction "2_2") (pintype "passive"))
      (node (ref "C40") (pin "2") (pinfunction "2_2") (pintype "passive"))
      (node (ref "C41") (pin "2") (pinfunction "2_2") (pintype "passive"))
      (node (ref "C42") (pin "2") (pinfunction "2_2") (pintype "passive"))
      (node (ref "C45") (pin "2") (pinfunction "2_2") (pintype "passive"))
      (node (ref "C46") (pin "2") (pinfunction "2_2") (pintype "passive"))
      (node (ref "C47") (pin "2") (pinfunction "2_2") (pintype "passive"))
      (node (ref "C48") (pin "2") (pinfunction "2_2") (pintype "passive"))
      (node (ref "C49") (pin "2") (pinfunction "2_2") (pintype "passive"))
      (node (ref "C5") (pin "-") (pinfunction "-_-") (pintype "passive"))
      (node (ref "C50") (pin "2") (pinfunction "2_2") (pintype "passive"))
      (node (ref "C51") (pin "-") (pinfunction "-_-") (pintype "passive"))
      (node (ref "C52") (pin "-") (pinfunction "-_-") (pintype "passive"))
      (node (ref "C53") (pin "2") (pinfunction "2_2") (pintype "passive"))
      (node (ref "C54") (pin "2") (pinfunction "2_2") (pintype "passive"))
      (node (ref "C55") (pin "2") (pinfunction "2_2") (pintype "passive"))
      (node (ref "C56") (pin "2") (pinfunction "2_2") (pintype "passive"))
      (node (ref "C57") (pin "2") (pinfunction "2_2") (pintype "passive"))
      (node (ref "C6") (pin "-") (pinfunction "-_-") (pintype "passive"))
      (node (ref "C7") (pin "-") (pinfunction "-_-") (pintype "passive"))
      (node (ref "C8") (pin "2") (pinfunction "2_2") (pintype "passive"))
      (node (ref "C9") (pin "2") (pinfunction "2_2") (pintype "passive"))
      (node (ref "IC1") (pin "2") (pinfunction "GND_2") (pintype "bidirectional"))
      (node (ref "IC2") (pin "1") (pinfunction "GND_1") (pintype "input"))
      (node (ref "IC3") (pin "1") (pinfunction "GND_1") (pintype "input"))
      (node (ref "IC4") (pin "P$11") (pinfunction "VSSRX_P$11") (pintype "input"))
      (node (ref "IC4") (pin "P$18") (pinfunction "VSSTX_P$18") (pintype "input"))
      (node (ref "IC4") (pin "P$2") (pinfunction "VSS_P$2") (pintype "input"))
      (node (ref "IC4") (pin "P$21") (pinfunction "VSSPLL_P$21") (pintype "input"))
      (node (ref "IC4") (pin "P$22") (pinfunction "VSSOSC_P$22") (pintype "input"))
      (node (ref "IC5") (pin "1") (pinfunction "GND_1") (pintype "power_in"))
      (node (ref "JP1") (pin "3") (pinfunction "3_3") (pintype "passive"))
      (node (ref "JP2") (pin "1") (pinfunction "1_1") (pintype "passive"))
      (node (ref "JP5") (pin "GND1") (pinfunction "GND_GND1") (pintype "bidirectional"))
      (node (ref "R21") (pin "1") (pinfunction "1_1") (pintype "passive"))
      (node (ref "R26") (pin "2") (pinfunction "2_2") (pintype "passive"))
      (node (ref "R27") (pin "2") (pinfunction "2_2") (pintype "passive"))
      (node (ref "R28") (pin "2") (pinfunction "2_2") (pintype "passive"))
      (node (ref "R29") (pin "2") (pinfunction "2_2") (pintype "passive"))
      (node (ref "R6") (pin "1") (pinfunction "1_1") (pintype "passive"))
      (node (ref "RJ1") (pin "G-") (pinfunction "G-_G-") (pintype "bidirectional"))
      (node (ref "RJ1") (pin "GND") (pinfunction "GND_GND") (pintype "bidirectional"))
      (node (ref "RJ1") (pin "SHIELD0") (pinfunction "SHIELD0_SHIELD0") (pintype "bidirectional"))
      (node (ref "RJ1") (pin "SHIELD1") (pinfunction "SHIELD1_SHIELD1") (pintype "bidirectional"))
      (node (ref "RJ1") (pin "Y-") (pinfunction "Y-_Y-") (pintype "bidirectional"))
      (node (ref "SV3") (pin "10") (pinfunction "10_10") (pintype "passive"))
      (node (ref "SV3") (pin "9") (pinfunction "9_9") (pintype "passive"))
      (node (ref "U$1") (pin "15") (pinfunction "VSS_15") (pintype "bidirectional"))
      (node (ref "U$1") (pin "31") (pinfunction "AVSS_31") (pintype "bidirectional"))
      (node (ref "U$1") (pin "36") (pinfunction "VSS_36") (pintype "bidirectional"))
      (node (ref "U$1") (pin "45") (pinfunction "VSS_45") (pintype "bidirectional"))
      (node (ref "U$1") (pin "65") (pinfunction "VSS_65") (pintype "bidirectional"))
      (node (ref "U$1") (pin "75") (pinfunction "VSS_75") (pintype "bidirectional"))
      (node (ref "U$2") (pin "4") (pinfunction "VSS_4") (pintype "bidirectional"))
      (node (ref "U1") (pin "6") (pinfunction "GND_6") (pintype "bidirectional"))
      (node (ref "U1") (pin "CD2") (pinfunction "SHIELD_CD2") (pintype "bidirectional"))
      (node (ref "U1") (pin "GND1") (pinfunction "SHIELD_GND1") (pintype "bidirectional"))
      (node (ref "U1") (pin "GND2") (pinfunction "SHIELD_GND2") (pintype "bidirectional"))
      (node (ref "U2") (pin "16") (pinfunction "DGND1_16") (pintype "power_in"))
      (node (ref "U2") (pin "20") (pinfunction "DGND2_20") (pintype "power_in"))
      (node (ref "U2") (pin "21") (pinfunction "DGND3_21") (pintype "power_in"))
      (node (ref "U2") (pin "22") (pinfunction "DGND4_22") (pintype "power_in"))
      (node (ref "U2") (pin "4") (pinfunction "DGND_4") (pintype "power_in"))
      (node (ref "X2") (pin "1") (pinfunction "S_1") (pintype "passive"))
      (node (ref "X3") (pin "4") (pinfunction "4_4") (pintype "passive"))
      (node (ref "X3") (pin "M1") (pinfunction "S1_M1") (pintype "passive"))
      (node (ref "X3") (pin "M2") (pinfunction "S2_M2") (pintype "passive"))
      (node (ref "X4") (pin "1") (pinfunction "S_1") (pintype "passive"))
      (node (ref "X5") (pin "2") (pinfunction "S_2") (pintype "passive"))
      (node (ref "Y1") (pin "2") (pinfunction "3_2") (pintype "passive"))
      (node (ref "Y1") (pin "4") (pinfunction "3_4") (pintype "passive"))
      (node (ref "Y2") (pin "2") (pinfunction "3_2") (pintype "passive"))
      (node (ref "Y2") (pin "4") (pinfunction "3_4") (pintype "passive"))
      (node (ref "Y3") (pin "2") (pinfunction "3_2") (pintype "passive"))
      (node (ref "Y3") (pin "4") (pinfunction "3_4") (pintype "passive"))
    )
    (net (code "8") (name "LEDA") (class "Default")
      (node (ref "IC4") (pin "P$27") (pinfunction "LEDA_P$27") (pintype "output"))
      (node (ref "R19") (pin "1") (pinfunction "1_1") (pintype "passive"))
    )
    (net (code "9") (name "LEDB") (class "Default")
      (node (ref "IC4") (pin "P$26") (pinfunction "LEDB_P$26") (pintype "output"))
      (node (ref "R17") (pin "2") (pinfunction "2_2") (pintype "passive"))
    )
    (net (code "10") (name "MCLR") (class "Default")
      (node (ref "C28") (pin "1") (pinfunction "1_1") (pintype "passive"))
      (node (ref "JP1") (pin "1") (pinfunction "1_1") (pintype "passive"))
      (node (ref "R9") (pin "1") (pinfunction "1_1") (pintype "passive"))
      (node (ref "U$1") (pin "13") (pinfunction "~{MCLR}_13") (pintype "bidirectional"))
    )
    (net (code "11") (name "MISO") (class "Default")
      (node (ref "IC4") (pin "P$6") (pinfunction "SO_P$6") (pintype "output"))
      (node (ref "U$1") (pin "33") (pinfunction "AN9/RP9/GD13/CN27/RB9_33") (pintype "bidirectional"))
      (node (ref "U$2") (pin "2") (pinfunction "SO_2") (pintype "bidirectional"))
      (node (ref "U1") (pin "7") (pinfunction "DO_7") (pintype "bidirectional"))
    )
    (net (code "12") (name "MOSI") (class "Default")
      (node (ref "IC4") (pin "P$7") (pinfunction "SI_P$7") (pintype "input"))
      (node (ref "U$1") (pin "32") (pinfunction "AN8/RP8/GD12/CN26/RB8_32") (pintype "bidirectional"))
      (node (ref "U$2") (pin "5") (pinfunction "SI_5") (pintype "bidirectional"))
      (node (ref "U1") (pin "3") (pinfunction "DI_3") (pintype "bidirectional"))
    )
    (net (code "13") (name "Net-(C14-Pad2)") (class "Default")
      (node (ref "C14") (pin "2") (pinfunction "2_2") (pintype "passive"))
      (node (ref "R2") (pin "1") (pinfunction "1_1") (pintype "passive"))
      (node (ref "R3") (pin "2") (pinfunction "2_2") (pintype "passive"))
    )
    (net (code "14") (name "Net-(C15-Pad2)") (class "Default")
      (node (ref "C15") (pin "2") (pinfunction "2_2") (pintype "passive"))
      (node (ref "L3") (pin "2") (pinfunction "2_2") (pintype "passive"))
      (node (ref "R4") (pin "2") (pinfunction "2_2") (pintype "passive"))
      (node (ref "R5") (pin "1") (pinfunction "1_1") (pintype "passive"))
      (node (ref "RJ1") (pin "P4") (pinfunction "P4_P4") (pintype "bidirectional"))
    )
    (net (code "15") (name "Net-(C30-Pad2)") (class "Default")
      (node (ref "C30") (pin "2") (pinfunction "2_2") (pintype "passive"))
      (node (ref "R23") (pin "1") (pinfunction "1_1") (pintype "passive"))
    )
    (net (code "16") (name "Net-(C33-Pad2)") (class "Default")
      (node (ref "C33") (pin "2") (pinfunction "2_2") (pintype "passive"))
      (node (ref "R24") (pin "1") (pinfunction "1_1") (pintype "passive"))
    )
    (net (code "17") (name "Net-(C36-Pad2)") (class "Default")
      (node (ref "C36") (pin "2") (pinfunction "2_2") (pintype "passive"))
      (node (ref "R22") (pin "1") (pinfunction "1_1") (pintype "passive"))
    )
    (net (code "18") (name "Net-(C43-Pad1)") (class "Default")
      (node (ref "C43") (pin "1") (pinfunction "1_1") (pintype "passive"))
      (node (ref "R31") (pin "1") (pinfunction "1_1") (pintype "passive"))
    )
    (net (code "19") (name "Net-(C44-Pad1)") (class "Default")
      (node (ref "C44") (pin "1") (pinfunction "1_1") (pintype "passive"))
      (node (ref "R32") (pin "1") (pinfunction "1_1") (pintype "passive"))
    )
    (net (code "20") (name "Net-(IC1-I{slash}O_1)") (class "Default")
      (node (ref "IC1") (pin "1") (pinfunction "I/O_1_1") (pintype "bidirectional"))
      (node (ref "X3") (pin "2") (pinfunction "2_2") (pintype "passive"))
    )
    (net (code "21") (name "Net-(IC1-I{slash}O_2)") (class "Default")
      (node (ref "IC1") (pin "3") (pinfunction "I/O_2_3") (pintype "bidirectional"))
      (node (ref "X3") (pin "3") (pinfunction "3_3") (pintype "passive"))
    )
    (net (code "22") (name "Net-(IC4-OSC1)") (class "Default")
      (node (ref "C21") (pin "1") (pinfunction "1_1") (pintype "passive"))
      (node (ref "IC4") (pin "P$23") (pinfunction "OSC1_P$23") (pintype "input"))
      (node (ref "Y2") (pin "1") (pinfunction "2_1") (pintype "passive"))
    )
    (net (code "23") (name "Net-(IC4-OSC2)") (class "Default")
      (node (ref "C22") (pin "1") (pinfunction "1_1") (pintype "passive"))
      (node (ref "IC4") (pin "P$24") (pinfunction "OSC2_P$24") (pintype "output"))
      (node (ref "Y2") (pin "3") (pinfunction "1_3") (pintype "passive"))
    )
    (net (code "24") (name "Net-(IC4-RBIAS)") (class "Default")
      (node (ref "IC4") (pin "P$14") (pinfunction "RBIAS_P$14") (pintype "input"))
      (node (ref "R6") (pin "2") (pinfunction "2_2") (pintype "passive"))
    )
    (net (code "25") (name "Net-(IC4-VCAP)") (class "Default")
      (node (ref "C24") (pin "+") (pinfunction "+_+") (pintype "passive"))
      (node (ref "IC4") (pin "P$1") (pinfunction "VCAP_P$1") (pintype "input"))
    )
    (net (code "26") (name "Net-(IC4-~{RESET})") (class "Default")
      (node (ref "IC4") (pin "P$10") (pinfunction "~{RESET}_P$10") (pintype "input"))
      (node (ref "R7") (pin "1") (pinfunction "1_1") (pintype "passive"))
    )
    (net (code "27") (name "Net-(JP3-LEFT)") (class "Default")
      (node (ref "C43") (pin "2") (pinfunction "2_2") (pintype "passive"))
      (node (ref "JP3") (pin "TIP") (pinfunction "LEFT_TIP") (pintype "bidirectional"))
      (node (ref "R34") (pin "1") (pinfunction "1_1") (pintype "passive"))
    )
    (net (code "28") (name "Net-(JP3-RIGHT)") (class "Default")
      (node (ref "C44") (pin "2") (pinfunction "2_2") (pintype "passive"))
      (node (ref "JP3") (pin "RING") (pinfunction "RIGHT_RING") (pintype "bidirectional"))
      (node (ref "R33") (pin "1") (pinfunction "1_1") (pintype "passive"))
    )
    (net (code "29") (name "Net-(JP5-VCC)") (class "Default")
      (node (ref "F1") (pin "1") (pinfunction "1_1") (pintype "passive"))
      (node (ref "JP5") (pin "VBUS1") (pinfunction "VCC_VBUS1") (pintype "bidirectional"))
    )
    (net (code "30") (name "Net-(LED1-PadC)") (class "Default")
      (node (ref "LED1") (pin "C") (pinfunction "C_C") (pintype "passive"))
      (node (ref "R14") (pin "2") (pinfunction "2_2") (pintype "passive"))
    )
    (net (code "31") (name "Net-(LED2-PadC)") (class "Default")
      (node (ref "LED2") (pin "C") (pinfunction "C_C") (pintype "passive"))
      (node (ref "R15") (pin "2") (pinfunction "2_2") (pintype "passive"))
    )
    (net (code "32") (name "Net-(LED3-PadC)") (class "Default")
      (node (ref "LED3") (pin "C") (pinfunction "C_C") (pintype "passive"))
      (node (ref "R16") (pin "2") (pinfunction "2_2") (pintype "passive"))
    )
    (net (code "33") (name "Net-(LED4-PadC)") (class "Default")
      (node (ref "LED4") (pin "C") (pinfunction "C_C") (pintype "passive"))
      (node (ref "R18") (pin "2") (pinfunction "2_2") (pintype "passive"))
    )
    (net (code "34") (name "Net-(R17-Pad1)") (class "Default")
      (node (ref "R17") (pin "1") (pinfunction "1_1") (pintype "passive"))
      (node (ref "RJ1") (pin "Y+") (pinfunction "Y+_Y+") (pintype "bidirectional"))
    )
    (net (code "35") (name "Net-(R19-Pad2)") (class "Default")
      (node (ref "R19") (pin "2") (pinfunction "2_2") (pintype "passive"))
      (node (ref "RJ1") (pin "G+") (pinfunction "G+_G+") (pintype "bidirectional"))
    )
    (net (code "36") (name "Net-(U$1-AN2{slash}C2INB{slash}VMIO{slash}RP13{slash}GD6{slash}CN4{slash}RB2)") (class "Default")
      (node (ref "R16") (pin "1") (pinfunction "1_1") (pintype "passive"))
      (node (ref "U$1") (pin "23") (pinfunction "AN2/C2INB/VMIO/RP13/GD6/CN4/RB2_23") (pintype "bidirectional"))
    )
    (net (code "37") (name "Net-(U$1-AN3{slash}C2INA{slash}GD5{slash}VPIO{slash}CN5{slash}RB3)") (class "Default")
      (node (ref "R18") (pin "1") (pinfunction "1_1") (pintype "passive"))
      (node (ref "U$1") (pin "22") (pinfunction "AN3/C2INA/GD5/VPIO/CN5/RB3_22") (pintype "bidirectional"))
    )
    (net (code "38") (name "Net-(U$1-PGEC1{slash}AN1{slash}VREF{slash}RP1{slash}CN3{slash}RB1)") (class "Default")
      (node (ref "R15") (pin "1") (pinfunction "1_1") (pintype "passive"))
      (node (ref "U$1") (pin "24") (pinfunction "PGEC1/AN1/VREF/RP1/CN3/RB1_24") (pintype "bidirectional"))
    )
    (net (code "39") (name "Net-(U$1-PGED1{slash}AN0{slash}VREF+{slash}RP0{slash}CN2{slash}RB0)") (class "Default")
      (node (ref "R14") (pin "1") (pinfunction "1_1") (pintype "passive"))
      (node (ref "U$1") (pin "25") (pinfunction "PGED1/AN0/VREF+/RP0/CN2/RB0_25") (pintype "bidirectional"))
    )
    (net (code "40") (name "Net-(U$1-VCAP)") (class "Default")
      (node (ref "C3") (pin "1") (pinfunction "1_1") (pintype "passive"))
      (node (ref "U$1") (pin "85") (pinfunction "VCAP_85") (pintype "bidirectional"))
    )
    (net (code "41") (name "Net-(U$2-~{CE})") (class "Default")
      (node (ref "R12") (pin "2") (pinfunction "2_2") (pintype "passive"))
      (node (ref "R13") (pin "1") (pinfunction "1_1") (pintype "passive"))
      (node (ref "U$2") (pin "1") (pinfunction "~{CE}_1") (pintype "bidirectional"))
    )
    (net (code "42") (name "Net-(U2A-GBUF)") (class "Default")
      (node (ref "R23") (pin "2") (pinfunction "2_2") (pintype "passive"))
      (node (ref "U2") (pin "42") (pinfunction "GBUF_42") (pintype "bidirectional"))
    )
    (net (code "43") (name "Net-(U2A-GPIO0)") (class "Default")
      (node (ref "R26") (pin "1") (pinfunction "1_1") (pintype "passive"))
      (node (ref "U2") (pin "33") (pinfunction "GPIO0_33") (pintype "bidirectional"))
    )
    (net (code "44") (name "Net-(U2A-GPIO1)") (class "Default")
      (node (ref "R27") (pin "1") (pinfunction "1_1") (pintype "passive"))
      (node (ref "U2") (pin "34") (pinfunction "GPIO1_34") (pintype "bidirectional"))
    )
    (net (code "45") (name "Net-(U2A-GPIO2{slash}DCLK)") (class "Default")
      (node (ref "R28") (pin "1") (pinfunction "1_1") (pintype "passive"))
      (node (ref "U2") (pin "9") (pinfunction "GPIO2/DCLK_9") (pintype "bidirectional"))
    )
    (net (code "46") (name "Net-(U2A-GPIO3{slash}SDATA)") (class "Default")
      (node (ref "R29") (pin "1") (pinfunction "1_1") (pintype "passive"))
      (node (ref "U2") (pin "10") (pinfunction "GPIO3/SDATA_10") (pintype "bidirectional"))
    )
    (net (code "47") (name "Net-(U2A-LEFT)") (class "Default")
      (node (ref "R22") (pin "2") (pinfunction "2_2") (pintype "passive"))
      (node (ref "R31") (pin "2") (pinfunction "2_2") (pintype "passive"))
      (node (ref "U2") (pin "46") (pinfunction "LEFT_46") (pintype "bidirectional"))
    )
    (net (code "48") (name "Net-(U2A-RCAP)") (class "Default")
      (node (ref "R25") (pin "2") (pinfunction "2_2") (pintype "passive"))
      (node (ref "U2") (pin "44") (pinfunction "RCAP_44") (pintype "bidirectional"))
    )
    (net (code "49") (name "Net-(U2A-RIGHT)") (class "Default")
      (node (ref "R24") (pin "2") (pinfunction "2_2") (pintype "passive"))
      (node (ref "R32") (pin "2") (pinfunction "2_2") (pintype "passive"))
      (node (ref "U2") (pin "39") (pinfunction "RIGHT_39") (pintype "bidirectional"))
    )
    (net (code "50") (name "Net-(U2A-RX)") (class "Default")
      (node (ref "R30") (pin "1") (pinfunction "1_1") (pintype "passive"))
      (node (ref "U2") (pin "26") (pinfunction "RX_26") (pintype "bidirectional"))
    )
    (net (code "51") (name "Net-(U2A-XTALI)") (class "Default")
      (node (ref "C50") (pin "1") (pinfunction "1_1") (pintype "passive"))
      (node (ref "R35") (pin "2") (pinfunction "2_2") (pintype "passive"))
      (node (ref "U2") (pin "18") (pinfunction "XTALI_18") (pintype "bidirectional"))
      (node (ref "Y3") (pin "1") (pinfunction "2_1") (pintype "passive"))
    )
    (net (code "52") (name "Net-(U2A-XTALO)") (class "Default")
      (node (ref "C49") (pin "1") (pinfunction "1_1") (pintype "passive"))
      (node (ref "R35") (pin "1") (pinfunction "1_1") (pintype "passive"))
      (node (ref "U2") (pin "17") (pinfunction "XTALO_17") (pintype "bidirectional"))
      (node (ref "Y3") (pin "3") (pinfunction "1_3") (pintype "passive"))
    )
    (net (code "53") (name "OSC1") (class "Default")
      (node (ref "C2") (pin "1") (pinfunction "1_1") (pintype "passive"))
      (node (ref "U$1") (pin "63") (pinfunction "OSCI/CLKI/CN23/RC12_63") (pintype "bidirectional"))
      (node (ref "Y1") (pin "1") (pinfunction "2_1") (pintype "passive"))
    )
    (net (code "54") (name "OSC2") (class "Default")
      (node (ref "C1") (pin "1") (pinfunction "1_1") (pintype "passive"))
      (node (ref "U$1") (pin "64") (pinfunction "OSCO/CLKO/CN22/RC15_64") (pintype "bidirectional"))
      (node (ref "Y1") (pin "3") (pinfunction "1_3") (pintype "passive"))
    )
    (net (code "55") (name "PGEC") (class "Default")
      (node (ref "JP1") (pin "5") (pinfunction "5_5") (pintype "passive"))
      (node (ref "U$1") (pin "20") (pinfunction "PGEC3/AN5/C1INA/VBUSON/RP18/CN7/RB5_20") (pintype "bidirectional"))
    )
    (net (code "56") (name "PGED") (class "Default")
      (node (ref "JP1") (pin "4") (pinfunction "4_4") (pintype "passive"))
      (node (ref "U$1") (pin "21") (pinfunction "PGED3/AN4/C1INB/USBOEN/RP28/GD4/CN6/RB4_21") (pintype "bidirectional"))
    )
    (net (code "57") (name "RA6") (class "Default")
      (node (ref "SV1") (pin "16") (pinfunction "16_16") (pintype "passive"))
      (node (ref "U$1") (pin "91") (pinfunction "AN23/GEN/CN39/RA6_91") (pintype "bidirectional"))
    )
    (net (code "58") (name "RA7") (class "Default")
      (node (ref "SV1") (pin "15") (pinfunction "15_15") (pintype "passive"))
      (node (ref "U$1") (pin "92") (pinfunction "AN22/PMA17/CN40/RA7_92") (pintype "bidirectional"))
    )
    (net (code "59") (name "RA14") (class "Default")
      (node (ref "SV1") (pin "2") (pinfunction "2_2") (pintype "passive"))
      (node (ref "U$1") (pin "66") (pinfunction "SCL1/RPI36/PMA22/PMCS2/CN43/RA14_66") (pintype "bidirectional"))
    )
    (net (code "60") (name "RA15") (class "Default")
      (node (ref "SV1") (pin "1") (pinfunction "1_1") (pintype "passive"))
      (node (ref "U$1") (pin "67") (pinfunction "SDA1/RPI35/PMBE1/CN44/RA15_67") (pintype "bidirectional"))
    )
    (net (code "61") (name "RB12") (class "Default")
      (node (ref "SV3") (pin "1") (pinfunction "1_1") (pintype "passive"))
      (node (ref "U$1") (pin "41") (pinfunction "AN12/PMA11/CTEDG2/CN30/RB12_41") (pintype "bidirectional"))
    )
    (net (code "62") (name "RD0") (class "Default")
      (node (ref "SV1") (pin "8") (pinfunction "8_8") (pintype "passive"))
      (node (ref "U$1") (pin "72") (pinfunction "DMH/RP11/INT0/CN49/RD0_72") (pintype "bidirectional"))
    )
    (net (code "63") (name "RD1") (class "Default")
      (node (ref "SV1") (pin "7") (pinfunction "7_7") (pintype "passive"))
      (node (ref "U$1") (pin "76") (pinfunction "VCPCON/RP24/GD7/VBUSCHG/CN50/RD1_76") (pintype "bidirectional"))
    )
    (net (code "64") (name "RD2") (class "Default")
      (node (ref "SV1") (pin "10") (pinfunction "10_10") (pintype "passive"))
      (node (ref "U$1") (pin "77") (pinfunction "DPH/RP23/GD11/PMACK1/CN51/RD2_77") (pintype "bidirectional"))
    )
    (net (code "65") (name "RD3") (class "Default")
      (node (ref "SV1") (pin "9") (pinfunction "9_9") (pintype "passive"))
      (node (ref "U$1") (pin "78") (pinfunction "RP22/PMBE0/CN52/RD3_78") (pintype "bidirectional"))
    )
    (net (code "66") (name "RD8") (class "Default")
      (node (ref "SV1") (pin "4") (pinfunction "4_4") (pintype "passive"))
      (node (ref "U$1") (pin "68") (pinfunction "DMLN/RTCC/RP2/CN53/RD8_68") (pintype "bidirectional"))
    )
    (net (code "67") (name "RD9") (class "Default")
      (node (ref "SV1") (pin "3") (pinfunction "3_3") (pintype "passive"))
      (node (ref "U$1") (pin "69") (pinfunction "DPLN/RP4/GD10/PMACK2/CN54/RD9_69") (pintype "bidirectional"))
    )
    (net (code "68") (name "RD10") (class "Default")
      (node (ref "SV1") (pin "6") (pinfunction "6_6") (pintype "passive"))
      (node (ref "U$1") (pin "70") (pinfunction "RP3/PMA15/PMCS2/CN55/RD10_70") (pintype "bidirectional"))
    )
    (net (code "69") (name "RD11") (class "Default")
      (node (ref "SV1") (pin "5") (pinfunction "5_5") (pintype "passive"))
      (node (ref "U$1") (pin "71") (pinfunction "RP12/PMA14/PMCS1/CN56/RD11_71") (pintype "bidirectional"))
    )
    (net (code "70") (name "RD12") (class "Default")
      (node (ref "SV1") (pin "12") (pinfunction "12_12") (pintype "passive"))
      (node (ref "U$1") (pin "79") (pinfunction "RPI42/PMD12/CN57/RD12_79") (pintype "bidirectional"))
    )
    (net (code "71") (name "RD14") (class "Default")
      (node (ref "SV3") (pin "2") (pinfunction "2_2") (pintype "passive"))
      (node (ref "U$1") (pin "47") (pinfunction "RPI43/GD14/CN20/RD14_47") (pintype "bidirectional"))
    )
    (net (code "72") (name "RD15") (class "Default")
      (node (ref "SV3") (pin "3") (pinfunction "3_3") (pintype "passive"))
      (node (ref "U$1") (pin "48") (pinfunction "RP5/GD15/CN21/RD15_48") (pintype "bidirectional"))
    )
    (net (code "73") (name "RE0") (class "Default")
      (node (ref "SV1") (pin "18") (pinfunction "18_18") (pintype "passive"))
      (node (ref "U$1") (pin "93") (pinfunction "PMD0/CN58/RE0_93") (pintype "bidirectional"))
    )
    (net (code "74") (name "RE1") (class "Default")
      (node (ref "SV1") (pin "17") (pinfunction "17_17") (pintype "passive"))
      (node (ref "U$1") (pin "94") (pinfunction "PMD1/CN59/RE1_94") (pintype "bidirectional"))
    )
    (net (code "75") (name "RE2") (class "Default")
      (node (ref "SV1") (pin "21") (pinfunction "21_21") (pintype "passive"))
      (node (ref "U$1") (pin "98") (pinfunction "PMD2/CN60/RE2_98") (pintype "bidirectional"))
    )
    (net (code "76") (name "RE3") (class "Default")
      (node (ref "SV1") (pin "24") (pinfunction "24_24") (pintype "passive"))
      (node (ref "U$1") (pin "99") (pinfunction "PMD3/CN61/RE3_99") (pintype "bidirectional"))
    )
    (net (code "77") (name "RE4") (class "Default")
      (node (ref "SV1") (pin "23") (pinfunction "23_23") (pintype "passive"))
      (node (ref "U$1") (pin "100") (pinfunction "PMD4/CN62/RE4_100") (pintype "bidirectional"))
    )
    (net (code "78") (name "RE5") (class "Default")
      (node (ref "SV1") (pin "26") (pinfunction "26_26") (pintype "passive"))
      (node (ref "U$1") (pin "3") (pinfunction "PMD5/CN63/RE5_3") (pintype "bidirectional"))
    )
    (net (code "79") (name "RE6") (class "Default")
      (node (ref "SV1") (pin "25") (pinfunction "25_25") (pintype "passive"))
      (node (ref "U$1") (pin "4") (pinfunction "SCL3/PMD6/CN64/RE6_4") (pintype "bidirectional"))
    )
    (net (code "80") (name "RF0") (class "Default")
      (node (ref "SV1") (pin "11") (pinfunction "11_11") (pintype "passive"))
      (node (ref "U$1") (pin "87") (pinfunction "VBUSST/VCMPST1/VBUSVLD/PMD11/CN68/RF0_87") (pintype "bidirectional"))
    )
    (net (code "81") (name "RF1") (class "Default")
      (node (ref "SV1") (pin "14") (pinfunction "14_14") (pintype "passive"))
      (node (ref "U$1") (pin "88") (pinfunction "VCMPST2/SESSVLD/PMD10/CN69/RF1_88") (pintype "bidirectional"))
    )
    (net (code "82") (name "RF2") (class "Default")
      (node (ref "SV3") (pin "7") (pinfunction "7_7") (pintype "passive"))
      (node (ref "U$1") (pin "52") (pinfunction "RP30/GD3/CN70/RF2_52") (pintype "bidirectional"))
    )
    (net (code "83") (name "RF3") (class "Default")
      (node (ref "SV3") (pin "6") (pinfunction "6_6") (pintype "passive"))
      (node (ref "U$1") (pin "51") (pinfunction "RP16/USBID/CN71/RF3_51") (pintype "bidirectional"))
    )
    (net (code "84") (name "RF4") (class "Default")
      (node (ref "SV3") (pin "4") (pinfunction "4_4") (pintype "passive"))
      (node (ref "U$1") (pin "49") (pinfunction "RP10/PMA9/CN17/RF4_49") (pintype "bidirectional"))
    )
    (net (code "85") (name "RF5") (class "Default")
      (node (ref "SV3") (pin "5") (pinfunction "5_5") (pintype "passive"))
      (node (ref "U$1") (pin "50") (pinfunction "RP17/PMA8/CN18/RF5_50") (pintype "bidirectional"))
    )
    (net (code "86") (name "RF8") (class "Default")
      (node (ref "SV3") (pin "8") (pinfunction "8_8") (pintype "passive"))
      (node (ref "U$1") (pin "53") (pinfunction "RP15/GD9/CN74/RF8_53") (pintype "bidirectional"))
    )
    (net (code "87") (name "RG1") (class "Default")
      (node (ref "SV1") (pin "13") (pinfunction "13_13") (pintype "passive"))
      (node (ref "U$1") (pin "89") (pinfunction "PMD9/CN78/RG1_89") (pintype "bidirectional"))
    )
    (net (code "88") (name "RG12") (class "Default")
      (node (ref "SV1") (pin "19") (pinfunction "19_19") (pintype "passive"))
      (node (ref "U$1") (pin "96") (pinfunction "VSYNC/CN79/RG12_96") (pintype "bidirectional"))
    )
    (net (code "89") (name "RG13") (class "Default")
      (node (ref "SV1") (pin "22") (pinfunction "22_22") (pintype "passive"))
      (node (ref "U$1") (pin "97") (pinfunction "HSYNC/CN80/RG13_97") (pintype "bidirectional"))
    )
    (net (code "90") (name "RG14") (class "Default")
      (node (ref "SV1") (pin "20") (pinfunction "20_20") (pintype "passive"))
      (node (ref "U$1") (pin "95") (pinfunction "PMA16/CN81/RG14_95") (pintype "bidirectional"))
    )
    (net (code "91") (name "RXD") (class "Default")
      (node (ref "JP2") (pin "3") (pinfunction "3_3") (pintype "passive"))
      (node (ref "U$1") (pin "40") (pinfunction "RPI32/PMA18/PMA5/CN75/RF12_40") (pintype "bidirectional"))
    )
    (net (code "92") (name "SCK") (class "Default")
      (node (ref "IC4") (pin "P$8") (pinfunction "SCK_P$8") (pintype "input"))
      (node (ref "U$1") (pin "27") (pinfunction "PGED2/AN7/RP7/RCV/GPWR/CN25/RB7_27") (pintype "bidirectional"))
      (node (ref "U$2") (pin "6") (pinfunction "SCK_6") (pintype "bidirectional"))
      (node (ref "U1") (pin "5") (pinfunction "SCK_5") (pintype "bidirectional"))
    )
    (net (code "93") (name "SD_CS") (class "Default")
      (node (ref "R11") (pin "1") (pinfunction "1_1") (pintype "passive"))
      (node (ref "U$1") (pin "34") (pinfunction "AN10/CVREF/PMA13/CN28/RB10_34") (pintype "bidirectional"))
      (node (ref "U1") (pin "2") (pinfunction "CS_2") (pintype "bidirectional"))
    )
    (net (code "94") (name "SD_PRESENT") (class "Default")
      (node (ref "R8") (pin "1") (pinfunction "1_1") (pintype "passive"))
      (node (ref "U$1") (pin "35") (pinfunction "AN11/PMA12/CN29/RB11_35") (pintype "bidirectional"))
      (node (ref "U1") (pin "CD1") (pinfunction "SHIELD_CD1") (pintype "bidirectional"))
    )
    (net (code "95") (name "SOSCI") (class "Default")
      (node (ref "C20") (pin "2") (pinfunction "2_2") (pintype "passive"))
      (node (ref "U$1") (pin "73") (pinfunction "SOSCI/C3IND/CN1/RC13_73") (pintype "bidirectional"))
      (node (ref "X1") (pin "1") (pinfunction "1_1") (pintype "passive"))
    )
    (net (code "96") (name "SOSCO") (class "Default")
      (node (ref "C23") (pin "2") (pinfunction "2_2") (pintype "passive"))
      (node (ref "U$1") (pin "74") (pinfunction "SOSCO/SCLKI/T1CK/C3INC/RPI37/CN0/RC14_74") (pintype "bidirectional"))
      (node (ref "X1") (pin "2") (pinfunction "2_2") (pintype "passive"))
    )
    (net (code "97") (name "TPIN_N") (class "Default")
      (node (ref "IC4") (pin "P$12") (pinfunction "TPIN-_P$12") (pintype "input"))
      (node (ref "R2") (pin "2") (pinfunction "2_2") (pintype "passive"))
      (node (ref "RJ1") (pin "RD-") (pinfunction "RD-_RD-") (pintype "bidirectional"))
    )
    (net (code "98") (name "TPIN_P") (class "Default")
      (node (ref "IC4") (pin "P$13") (pinfunction "TPIN+_P$13") (pintype "input"))
      (node (ref "R3") (pin "1") (pinfunction "1_1") (pintype "passive"))
      (node (ref "RJ1") (pin "RD+") (pinfunction "RD+_RD+") (pintype "bidirectional"))
    )
    (net (code "99") (name "TPOUT_N") (class "Default")
      (node (ref "IC4") (pin "P$16") (pinfunction "TPOUT-_P$16") (pintype "output"))
      (node (ref "R5") (pin "2") (pinfunction "2_2") (pintype "passive"))
      (node (ref "RJ1") (pin "TD-") (pinfunction "TD-_TD-") (pintype "bidirectional"))
    )
    (net (code "100") (name "TPOUT_P") (class "Default")
      (node (ref "IC4") (pin "P$17") (pinfunction "TPOUT+_P$17") (pintype "output"))
      (node (ref "R4") (pin "1") (pinfunction "1_1") (pintype "passive"))
      (node (ref "RJ1") (pin "TD+") (pinfunction "TD+_TD+") (pintype "bidirectional"))
    )
    (net (code "101") (name "TXD") (class "Default")
      (node (ref "JP2") (pin "2") (pinfunction "2_2") (pintype "passive"))
      (node (ref "U$1") (pin "39") (pinfunction "RP31/GD2/CN76/RF13_39") (pintype "bidirectional"))
    )
    (net (code "102") (name "VBUS") (class "Default")
      (node (ref "C27") (pin "1") (pinfunction "1_1") (pintype "passive"))
      (node (ref "C52") (pin "+") (pinfunction "+_+") (pintype "passive"))
      (node (ref "C53") (pin "1") (pinfunction "1_1") (pintype "passive"))
      (node (ref "C6") (pin "+") (pinfunction "+_+") (pintype "passive"))
      (node (ref "C7") (pin "+") (pinfunction "+_+") (pintype "passive"))
      (node (ref "C8") (pin "1") (pinfunction "1_1") (pintype "passive"))
      (node (ref "F1") (pin "2") (pinfunction "2_2") (pintype "passive"))
      (node (ref "IC1") (pin "5") (pinfunction "VBUS_5") (pintype "bidirectional"))
      (node (ref "IC2") (pin "3") (pinfunction "IN_3") (pintype "input"))
      (node (ref "IC3") (pin "3") (pinfunction "IN_3") (pintype "input"))
      (node (ref "U$1") (pin "54") (pinfunction "VBUS/CN73/RF7_54") (pintype "bidirectional"))
      (node (ref "X3") (pin "1") (pinfunction "1_1") (pintype "passive"))
      (node (ref "X5") (pin "1") (pinfunction "S_1") (pintype "passive"))
    )
    (net (code "103") (name "VS_AGND") (class "Default")
      (node (ref "C12") (pin "2") (pinfunction "2_2") (pintype "passive"))
      (node (ref "C13") (pin "2") (pinfunction "2_2") (pintype "passive"))
      (node (ref "C19") (pin "2") (pinfunction "2_2") (pintype "passive"))
      (node (ref "C30") (pin "1") (pinfunction "1_1") (pintype "passive"))
      (node (ref "C33") (pin "1") (pinfunction "1_1") (pintype "passive"))
      (node (ref "C36") (pin "1") (pinfunction "1_1") (pintype "passive"))
      (node (ref "C58") (pin "2") (pinfunction "2_2") (pintype "passive"))
      (node (ref "JP3") (pin "SLEEVE") (pinfunction "SLEEVE_SLEEVE") (pintype "bidirectional"))
      (node (ref "R21") (pin "2") (pinfunction "2_2") (pintype "passive"))
      (node (ref "R25") (pin "1") (pinfunction "1_1") (pintype "passive"))
      (node (ref "R33") (pin "2") (pinfunction "2_2") (pintype "passive"))
      (node (ref "R34") (pin "2") (pinfunction "2_2") (pintype "passive"))
      (node (ref "U2") (pin "37") (pinfunction "AGND_37") (pintype "power_in"))
      (node (ref "U2") (pin "40") (pinfunction "AGND1_40") (pintype "power_in"))
      (node (ref "U2") (pin "41") (pinfunction "AGND2_41") (pintype "power_in"))
      (node (ref "U2") (pin "47") (pinfunction "AGND3_47") (pintype "power_in"))
    )
    (net (code "104") (name "VS_AVDD") (class "Default")
      (node (ref "C12") (pin "1") (pinfunction "1_1") (pintype "passive"))
      (node (ref "C13") (pin "1") (pinfunction "1_1") (pintype "passive"))
      (node (ref "C19") (pin "1") (pinfunction "1_1") (pintype "passive"))
      (node (ref "C58") (pin "1") (pinfunction "1_1") (pintype "passive"))
      (node (ref "L1") (pin "1") (pinfunction "1_1") (pintype "passive"))
      (node (ref "U2") (pin "38") (pinfunction "AVDD_38") (pintype "power_in"))
      (node (ref "U2") (pin "43") (pinfunction "AVDD1_43") (pintype "power_in"))
      (node (ref "U2") (pin "45") (pinfunction "AVDD2_45") (pintype "power_in"))
    )
    (net (code "105") (name "VS_CVDD") (class "Default")
      (node (ref "C45") (pin "1") (pinfunction "1_1") (pintype "passive"))
      (node (ref "C46") (pin "1") (pinfunction "1_1") (pintype "passive"))
      (node (ref "C47") (pin "1") (pinfunction "1_1") (pintype "passive"))
      (node (ref "C48") (pin "1") (pinfunction "1_1") (pintype "passive"))
      (node (ref "C57") (pin "1") (pinfunction "1_1") (pintype "passive"))
      (node (ref "L2") (pin "1") (pinfunction "1_1") (pintype "passive"))
      (node (ref "U2") (pin "24") (pinfunction "CVDD2_24") (pintype "power_in"))
      (node (ref "U2") (pin "31") (pinfunction "CVDD3_31") (pintype "power_in"))
      (node (ref "U2") (pin "5") (pinfunction "CVDD_5") (pintype "power_in"))
      (node (ref "U2") (pin "7") (pinfunction "CVDD1_7") (pintype "power_in"))
    )
    (net (code "106") (name "VS_DREQ") (class "Default")
      (node (ref "U$1") (pin "8") (pinfunction "RPI40/GD1/CN47/RC3_8") (pintype "bidirectional"))
      (node (ref "U2") (pin "8") (pinfunction "DREQ_8") (pintype "bidirectional"))
    )
    (net (code "107") (name "VS_MISO") (class "Default")
      (node (ref "U$1") (pin "9") (pinfunction "AN16/RPI41/PMCS2/PMA22(2)/CN48/RC4_9") (pintype "bidirectional"))
      (node (ref "U2") (pin "30") (pinfunction "SO_30") (pintype "bidirectional"))
    )
    (net (code "108") (name "VS_MOSI") (class "Default")
      (node (ref "U$1") (pin "11") (pinfunction "AN18/C1INC/RP26/PMA4/PMA20(2)/CN9/RG7_11") (pintype "bidirectional"))
      (node (ref "U2") (pin "29") (pinfunction "SI_29") (pintype "bidirectional"))
    )
    (net (code "109") (name "VS_SCK") (class "Default")
      (node (ref "U$1") (pin "10") (pinfunction "AN17/C1IND/RP21/PMA5/PMA18(2)/CN8/RG6_10") (pintype "bidirectional"))
      (node (ref "U2") (pin "28") (pinfunction "SCLK_28") (pintype "bidirectional"))
    )
    (net (code "110") (name "VS_XCS") (class "Default")
      (node (ref "U$1") (pin "7") (pinfunction "RPI39/GD8/CN46/RC2_7") (pintype "bidirectional"))
      (node (ref "U2") (pin "23") (pinfunction "XCS_23") (pintype "bidirectional"))
    )
    (net (code "111") (name "VS_XDCS") (class "Default")
      (node (ref "U$1") (pin "6") (pinfunction "RPI38/GD0/CN45/RC1_6") (pintype "bidirectional"))
      (node (ref "U2") (pin "13") (pinfunction "XDCS/BSYNC_13") (pintype "bidirectional"))
    )
    (net (code "112") (name "VS_XRST") (class "Default")
      (node (ref "R36") (pin "1") (pinfunction "1_1") (pintype "passive"))
      (node (ref "U$1") (pin "12") (pinfunction "AN19/C2IND/RP19/PMA3/PMA21(2)/CN10/RG8_12") (pintype "bidirectional"))
      (node (ref "U2") (pin "3") (pinfunction "XRESET_3") (pintype "bidirectional"))
    )
    (net (code "113") (name "_2V6") (class "Default")
      (node (ref "C51") (pin "+") (pinfunction "+_+") (pintype "passive"))
      (node (ref "C54") (pin "1") (pinfunction "1_1") (pintype "passive"))
      (node (ref "IC3") (pin "2") (pinfunction "OUT_2") (pintype "passive"))
      (node (ref "IC3") (pin "TAB") (pinfunction "OUT1_TAB") (pintype "passive"))
      (node (ref "L1") (pin "2") (pinfunction "2_2") (pintype "passive"))
      (node (ref "L2") (pin "2") (pinfunction "2_2") (pintype "passive"))
    )
    (net (code "114") (name "_3V") (class "Default")
      (node (ref "C10") (pin "+") (pinfunction "+_+") (pintype "passive"))
      (node (ref "C11") (pin "+") (pinfunction "+_+") (pintype "passive"))
      (node (ref "C16") (pin "1") (pinfunction "1_1") (pintype "passive"))
      (node (ref "C17") (pin "1") (pinfunction "1_1") (pintype "passive"))
      (node (ref "C18") (pin "1") (pinfunction "1_1") (pintype "passive"))
      (node (ref "C25") (pin "1") (pinfunction "1_1") (pintype "passive"))
      (node (ref "C26") (pin "1") (pinfunction "1_1") (pintype "passive"))
      (node (ref "C29") (pin "1") (pinfunction "1_1") (pintype "passive"))
      (node (ref "C31") (pin "1") (pinfunction "1_1") (pintype "passive"))
      (node (ref "C32") (pin "1") (pinfunction "1_1") (pintype "passive"))
      (node (ref "C34") (pin "1") (pinfunction "1_1") (pintype "passive"))
      (node (ref "C37") (pin "1") (pinfunction "1_1") (pintype "passive"))
      (node (ref "C38") (pin "1") (pinfunction "1_1") (pintype "passive"))
      (node (ref "C39") (pin "1") (pinfunction "1_1") (pintype "passive"))
      (node (ref "C4") (pin "1") (pinfunction "1_1") (pintype "passive"))
      (node (ref "C40") (pin "1") (pinfunction "1_1") (pintype "passive"))
      (node (ref "C41") (pin "1") (pinfunction "1_1") (pintype "passive"))
      (node (ref "C42") (pin "1") (pinfunction "1_1") (pintype "passive"))
      (node (ref "C5") (pin "+") (pinfunction "+_+") (pintype "passive"))
      (node (ref "C55") (pin "1") (pinfunction "1_1") (pintype "passive"))
      (node (ref "C56") (pin "1") (pinfunction "1_1") (pintype "passive"))
      (node (ref "C9") (pin "1") (pinfunction "1_1") (pintype "passive"))
      (node (ref "IC2") (pin "2") (pinfunction "OUT_2") (pintype "passive"))
      (node (ref "IC2") (pin "TAB") (pinfunction "OUT1_TAB") (pintype "passive"))
      (node (ref "IC4") (pin "P$15") (pinfunction "VDDTX_P$15") (pintype "input"))
      (node (ref "IC4") (pin "P$19") (pinfunction "VDDRX_P$19") (pintype "input"))
      (node (ref "IC4") (pin "P$20") (pinfunction "VDDPLL_P$20") (pintype "input"))
      (node (ref "IC4") (pin "P$25") (pinfunction "VDDOSC_P$25") (pintype "input"))
      (node (ref "IC4") (pin "P$28") (pinfunction "VDD_P$28") (pintype "input"))
      (node (ref "IC5") (pin "3") (pinfunction "VDD_3") (pintype "power_in"))
      (node (ref "JP2") (pin "4") (pinfunction "4_4") (pintype "passive"))
      (node (ref "L3") (pin "1") (pinfunction "1_1") (pintype "passive"))
      (node (ref "LED1") (pin "A") (pinfunction "A_A") (pintype "passive"))
      (node (ref "LED2") (pin "A") (pinfunction "A_A") (pintype "passive"))
      (node (ref "LED3") (pin "A") (pinfunction "A_A") (pintype "passive"))
      (node (ref "LED4") (pin "A") (pinfunction "A_A") (pintype "passive"))
      (node (ref "R1") (pin "2") (pinfunction "2_2") (pintype "passive"))
      (node (ref "R10") (pin "2") (pinfunction "2_2") (pintype "passive"))
      (node (ref "R11") (pin "2") (pinfunction "2_2") (pintype "passive"))
      (node (ref "R13") (pin "2") (pinfunction "2_2") (pintype "passive"))
      (node (ref "R20") (pin "1") (pinfunction "1_1") (pintype "passive"))
      (node (ref "R30") (pin "2") (pinfunction "2_2") (pintype "passive"))
      (node (ref "R36") (pin "2") (pinfunction "2_2") (pintype "passive"))
      (node (ref "R7") (pin "2") (pinfunction "2_2") (pintype "passive"))
      (node (ref "R8") (pin "2") (pinfunction "2_2") (pintype "passive"))
      (node (ref "R9") (pin "2") (pinfunction "2_2") (pintype "passive"))
      (node (ref "U$1") (pin "16") (pinfunction "VDD_16") (pintype "bidirectional"))
      (node (ref "U$1") (pin "2") (pinfunction "VDD_2") (pintype "bidirectional"))
      (node (ref "U$1") (pin "37") (pinfunction "VDD_37") (pintype "bidirectional"))
      (node (ref "U$1") (pin "46") (pinfunction "VDD_46") (pintype "bidirectional"))
      (node (ref "U$1") (pin "55") (pinfunction "VUSB_55") (pintype "bidirectional"))
      (node (ref "U$1") (pin "62") (pinfunction "VDD_62") (pintype "bidirectional"))
      (node (ref "U$1") (pin "86") (pinfunction "ENVREG_86") (pintype "bidirectional"))
      (node (ref "U$2") (pin "3") (pinfunction "~{WP}_3") (pintype "bidirectional"))
      (node (ref "U$2") (pin "7") (pinfunction "~{HOLD}_7") (pintype "bidirectional"))
      (node (ref "U$2") (pin "8") (pinfunction "VDD_8") (pintype "bidirectional"))
      (node (ref "U1") (pin "4") (pinfunction "VCC_4") (pintype "bidirectional"))
      (node (ref "U2") (pin "14") (pinfunction "IOVDD1_14") (pintype "power_in"))
      (node (ref "U2") (pin "19") (pinfunction "IOVDD2_19") (pintype "power_in"))
      (node (ref "U2") (pin "32") (pinfunction "TEST_32") (pintype "bidirectional"))
      (node (ref "U2") (pin "6") (pinfunction "IOVDD_6") (pintype "power_in"))
      (node (ref "X2") (pin "2") (pinfunction "S_2") (pintype "passive"))
      (node (ref "X4") (pin "2") (pinfunction "S_2") (pintype "passive"))
    )
    (net (code "115") (name "unconnected-(IC4-CLKOUT-PadP$3)") (class "Default")
      (node (ref "IC4") (pin "P$3") (pinfunction "CLKOUT_P$3") (pintype "output"))
    )
    (net (code "116") (name "unconnected-(IC4-NC*-PadP$5)") (class "Default")
      (node (ref "IC4") (pin "P$5") (pinfunction "NC*_P$5") (pintype "output"))
    )
    (net (code "117") (name "unconnected-(IC4-~{INT}-PadP$4)") (class "Default")
      (node (ref "IC4") (pin "P$4") (pinfunction "~{INT}_P$4") (pintype "output"))
    )
    (net (code "118") (name "unconnected-(JP1-Pad2)") (class "Default")
      (node (ref "JP1") (pin "2") (pinfunction "2_2") (pintype "passive"))
    )
    (net (code "119") (name "unconnected-(JP1-Pad6)") (class "Default")
      (node (ref "JP1") (pin "6") (pinfunction "6_6") (pintype "passive"))
    )
    (net (code "120") (name "unconnected-(JP5-D+-PadD+1)") (class "Default")
      (node (ref "JP5") (pin "D+1") (pinfunction "D+_D+1") (pintype "bidirectional"))
    )
    (net (code "121") (name "unconnected-(JP5-D--PadD-1)") (class "Default")
      (node (ref "JP5") (pin "D-1") (pinfunction "D-_D-1") (pintype "bidirectional"))
    )
    (net (code "122") (name "unconnected-(JP5-ID-PadID1)") (class "Default")
      (node (ref "JP5") (pin "ID1") (pinfunction "ID_ID1") (pintype "bidirectional"))
    )
    (net (code "123") (name "unconnected-(RJ1-PadNC)") (class "Default")
      (node (ref "RJ1") (pin "NC") (pinfunction "NC_NC") (pintype "bidirectional"))
    )
    (net (code "124") (name "unconnected-(RJ1-PadP5)") (class "Default")
      (node (ref "RJ1") (pin "P5") (pinfunction "P5_P5") (pintype "bidirectional"))
    )
    (net (code "125") (name "unconnected-(U$1-AN13{slash}PMA10{slash}CTEDG1{slash}CN31{slash}RB13-Pad42)") (class "Default")
      (node (ref "U$1") (pin "42") (pinfunction "AN13/PMA10/CTEDG1/CN31/RB13_42") (pintype "bidirectional"))
    )
    (net (code "126") (name "unconnected-(U$1-AN14{slash}CTPLS{slash}RP14{slash}PMA1{slash}CN32{slash}RB14-Pad43)") (class "Default")
      (node (ref "U$1") (pin "43") (pinfunction "AN14/CTPLS/RP14/PMA1/CN32/RB14_43") (pintype "bidirectional"))
    )
    (net (code "127") (name "unconnected-(U$1-AN15{slash}REFO{slash}RP29{slash}PMA0{slash}CN12{slash}RB15-Pad44)") (class "Default")
      (node (ref "U$1") (pin "44") (pinfunction "AN15/REFO/RP29/PMA0/CN12/RB15_44") (pintype "bidirectional"))
    )
    (net (code "128") (name "unconnected-(U$1-AN20{slash}C2INC{slash}RP27{slash}PMA2{slash}CN11{slash}RG9-Pad14)") (class "Default")
      (node (ref "U$1") (pin "14") (pinfunction "AN20/C2INC/RP27/PMA2/CN11/RG9_14") (pintype "bidirectional"))
    )
    (net (code "129") (name "unconnected-(U$1-AN21{slash}RPI34{slash}PMA19{slash}CN67{slash}RE9-Pad19)") (class "Default")
      (node (ref "U$1") (pin "19") (pinfunction "AN21/RPI34/PMA19/CN67/RE9_19") (pintype "bidirectional"))
    )
    (net (code "130") (name "unconnected-(U$1-C3INA{slash}SESSEND{slash}PMD15{slash}CN16{slash}RD7-Pad84)") (class "Default")
      (node (ref "U$1") (pin "84") (pinfunction "C3INA/SESSEND/PMD15/CN16/RD7_84") (pintype "bidirectional"))
    )
    (net (code "131") (name "unconnected-(U$1-C3INB{slash}PMD14{slash}CN15{slash}RD6-Pad83)") (class "Default")
      (node (ref "U$1") (pin "83") (pinfunction "C3INB/PMD14/CN15/RD6_83") (pintype "bidirectional"))
    )
    (net (code "132") (name "unconnected-(U$1-GCLK{slash}CN82{slash}RG15-Pad1)") (class "Default")
      (node (ref "U$1") (pin "1") (pinfunction "GCLK/CN82/RG15_1") (pintype "bidirectional"))
    )
    (net (code "133") (name "unconnected-(U$1-PMD8{slash}CN77{slash}RG0-Pad90)") (class "Default")
      (node (ref "U$1") (pin "90") (pinfunction "PMD8/CN77/RG0_90") (pintype "bidirectional"))
    )
    (net (code "134") (name "unconnected-(U$1-PMD13{slash}CN19{slash}RD13-Pad80)") (class "Default")
      (node (ref "U$1") (pin "80") (pinfunction "PMD13/CN19/RD13_80") (pintype "bidirectional"))
    )
    (net (code "135") (name "unconnected-(U$1-RP20{slash}PMRD{slash}CN14{slash}RD5-Pad82)") (class "Default")
      (node (ref "U$1") (pin "82") (pinfunction "RP20/PMRD/CN14/RD5_82") (pintype "bidirectional"))
    )
    (net (code "136") (name "unconnected-(U$1-RP25{slash}PMWR{slash}CN13{slash}RD4-Pad81)") (class "Default")
      (node (ref "U$1") (pin "81") (pinfunction "RP25/PMWR/CN13/RD4_81") (pintype "bidirectional"))
    )
    (net (code "137") (name "unconnected-(U$1-RPI33{slash}PMCS1{slash}CN66{slash}RE8-Pad18)") (class "Default")
      (node (ref "U$1") (pin "18") (pinfunction "RPI33/PMCS1/CN66/RE8_18") (pintype "bidirectional"))
    )
    (net (code "138") (name "unconnected-(U$1-SCL2{slash}CN35{slash}RA2-Pad58)") (class "Default")
      (node (ref "U$1") (pin "58") (pinfunction "SCL2/CN35/RA2_58") (pintype "bidirectional"))
    )
    (net (code "139") (name "unconnected-(U$1-SDA2{slash}PMA20{slash}PMA4{slash}CN36{slash}RA3-Pad59)") (class "Default")
      (node (ref "U$1") (pin "59") (pinfunction "SDA2/PMA20/PMA4/CN36/RA3_59") (pintype "bidirectional"))
    )
    (net (code "140") (name "unconnected-(U$1-TDI{slash}PMA21{slash}PMA3{slash}CN37{slash}RA4-Pad60)") (class "Default")
      (node (ref "U$1") (pin "60") (pinfunction "TDI/PMA21/PMA3/CN37/RA4_60") (pintype "bidirectional"))
    )
    (net (code "141") (name "unconnected-(U$1-TDO{slash}CN38{slash}RA5-Pad61)") (class "Default")
      (node (ref "U$1") (pin "61") (pinfunction "TDO/CN38/RA5_61") (pintype "bidirectional"))
    )
    (net (code "142") (name "unconnected-(U$1-TMS{slash}CN33{slash}RA0-Pad17)") (class "Default")
      (node (ref "U$1") (pin "17") (pinfunction "TMS/CN33/RA0_17") (pintype "bidirectional"))
    )
    (net (code "143") (name "unconnected-(U$1-VREF+{slash}PMA6{slash}CN42{slash}RA10-Pad29)") (class "Default")
      (node (ref "U$1") (pin "29") (pinfunction "VREF+/PMA6/CN42/RA10_29") (pintype "bidirectional"))
    )
    (net (code "144") (name "unconnected-(U$1-VREF-{slash}PMA7{slash}CN41{slash}RA9-Pad28)") (class "Default")
      (node (ref "U$1") (pin "28") (pinfunction "VREF-/PMA7/CN41/RA9_28") (pintype "bidirectional"))
    )
    (net (code "145") (name "unconnected-(U1-NC-Pad1)") (class "Default")
      (node (ref "U1") (pin "1") (pinfunction "NC_1") (pintype "bidirectional"))
    )
    (net (code "146") (name "unconnected-(U1-RSV-Pad8)") (class "Default")
      (node (ref "U1") (pin "8") (pinfunction "RSV_8") (pintype "bidirectional"))
    )
    (net (code "147") (name "unconnected-(U2A-LINEIN-Pad48)") (class "Default")
      (node (ref "U2") (pin "48") (pinfunction "LINEIN_48") (pintype "bidirectional"))
    )
    (net (code "148") (name "unconnected-(U2A-MICN-Pad2)") (class "Default")
      (node (ref "U2") (pin "2") (pinfunction "MICN_2") (pintype "bidirectional"))
    )
    (net (code "149") (name "unconnected-(U2A-MICP-Pad1)") (class "Default")
      (node (ref "U2") (pin "1") (pinfunction "MICP_1") (pintype "bidirectional"))
    )
    (net (code "150") (name "unconnected-(U2A-TX-Pad27)") (class "Default")
      (node (ref "U2") (pin "27") (pinfunction "TX_27") (pintype "bidirectional"))
    )
    (net (code "151") (name "unconnected-(U2A-VCO-Pad15)") (class "Default")
      (node (ref "U2") (pin "15") (pinfunction "VCO_15") (pintype "bidirectional"))
    )
  )
)
